# ph_v6.net
KiCad netlist of a schematic drawn in EAGLE
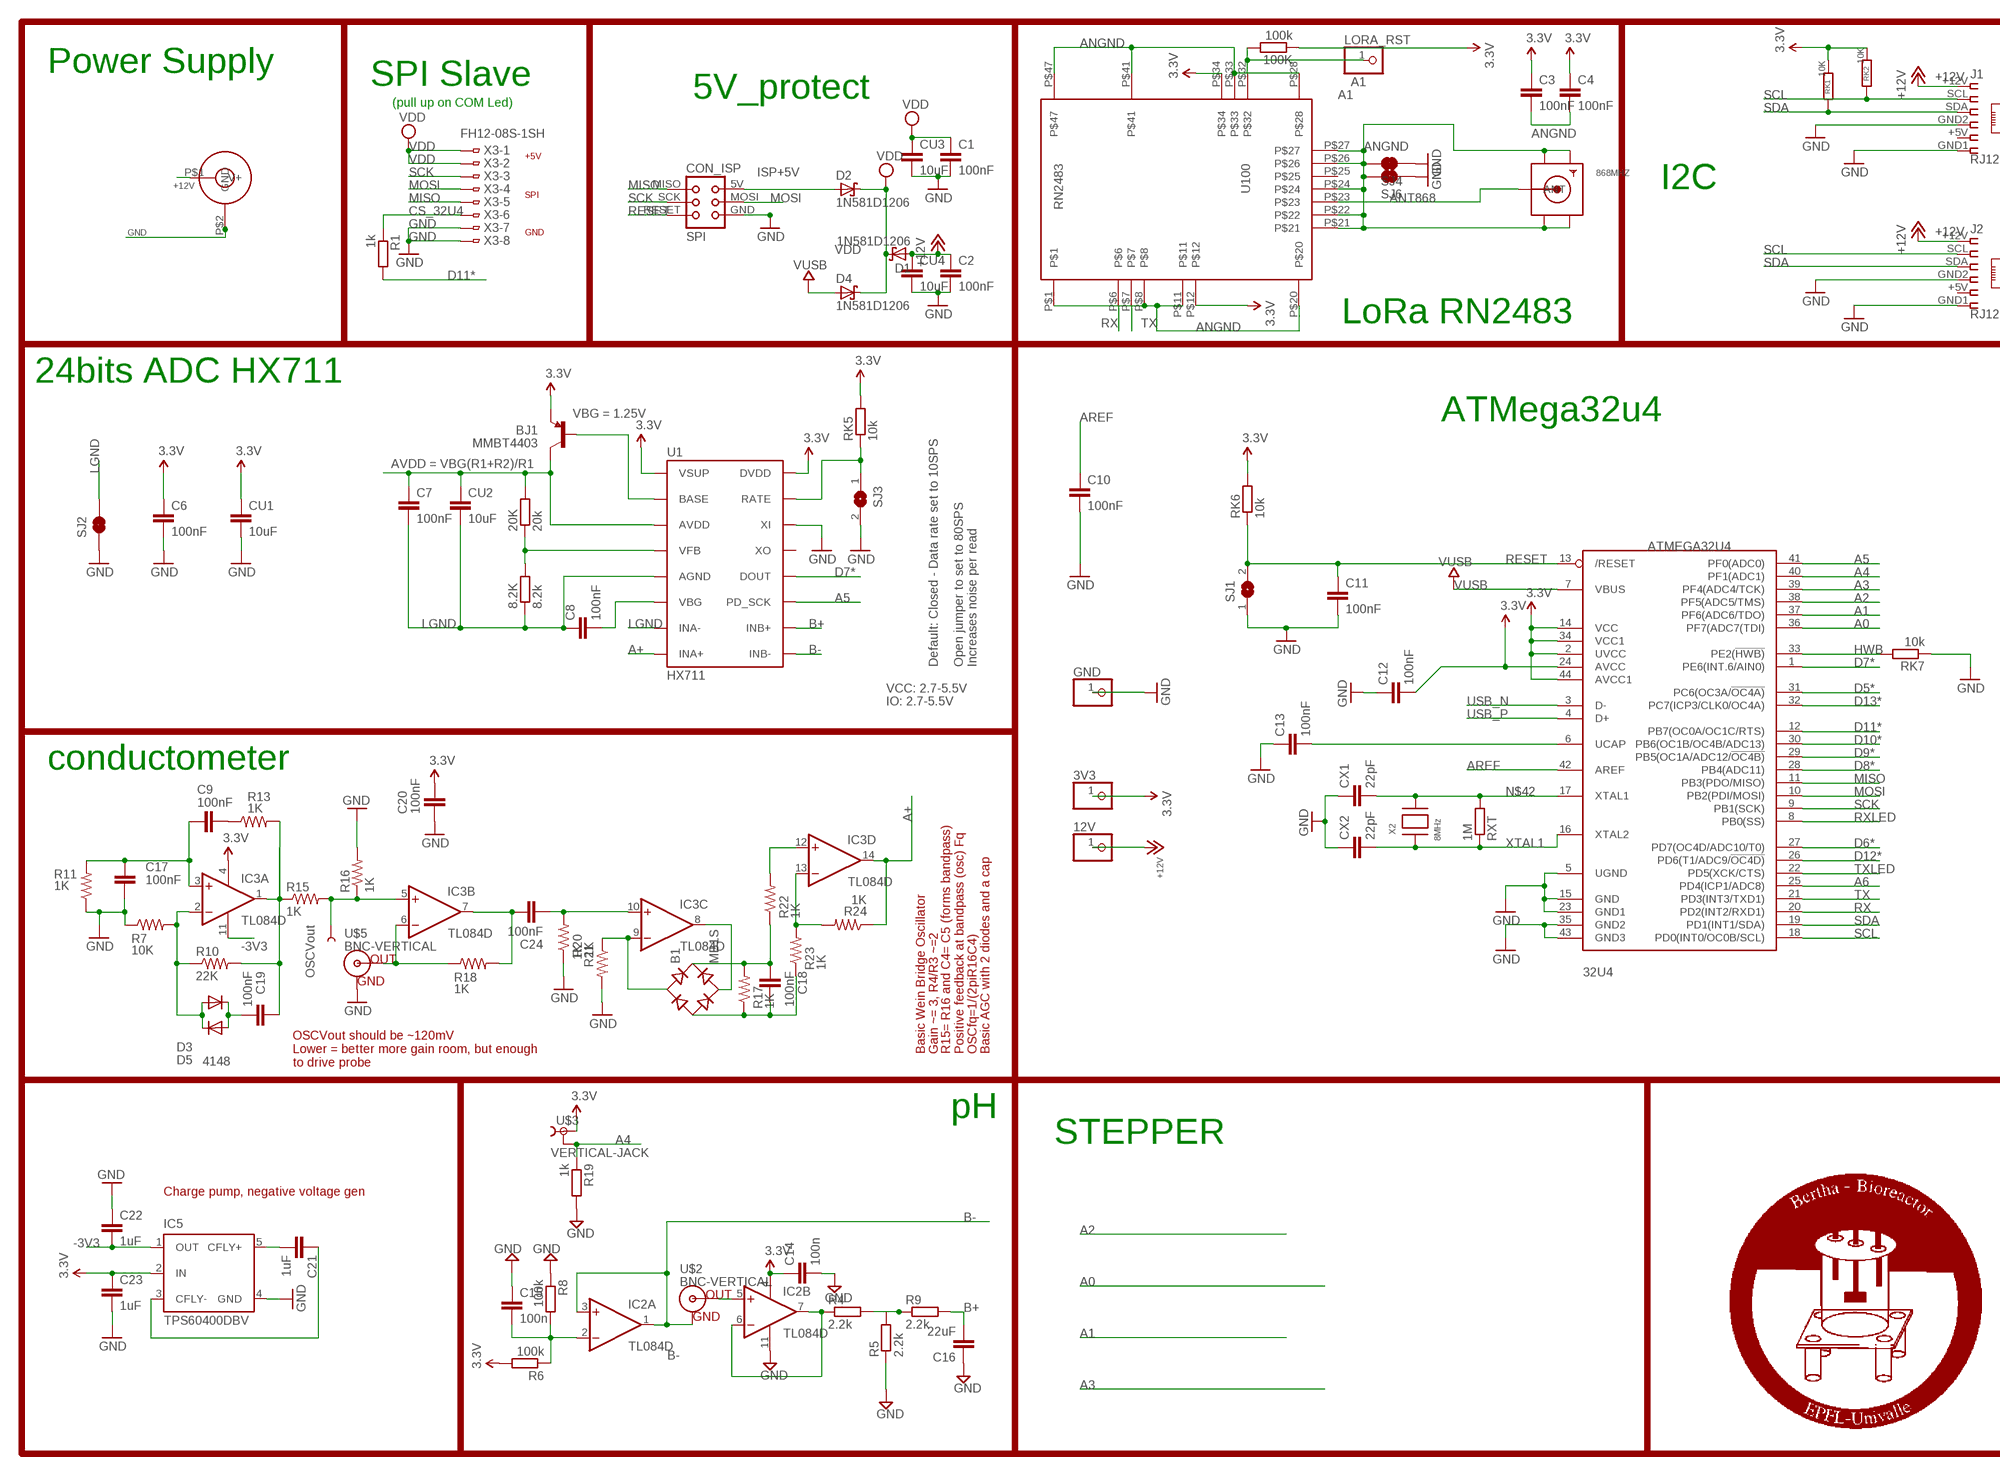
[diagram p0: schematic, sheet 1, part 1 of 2]
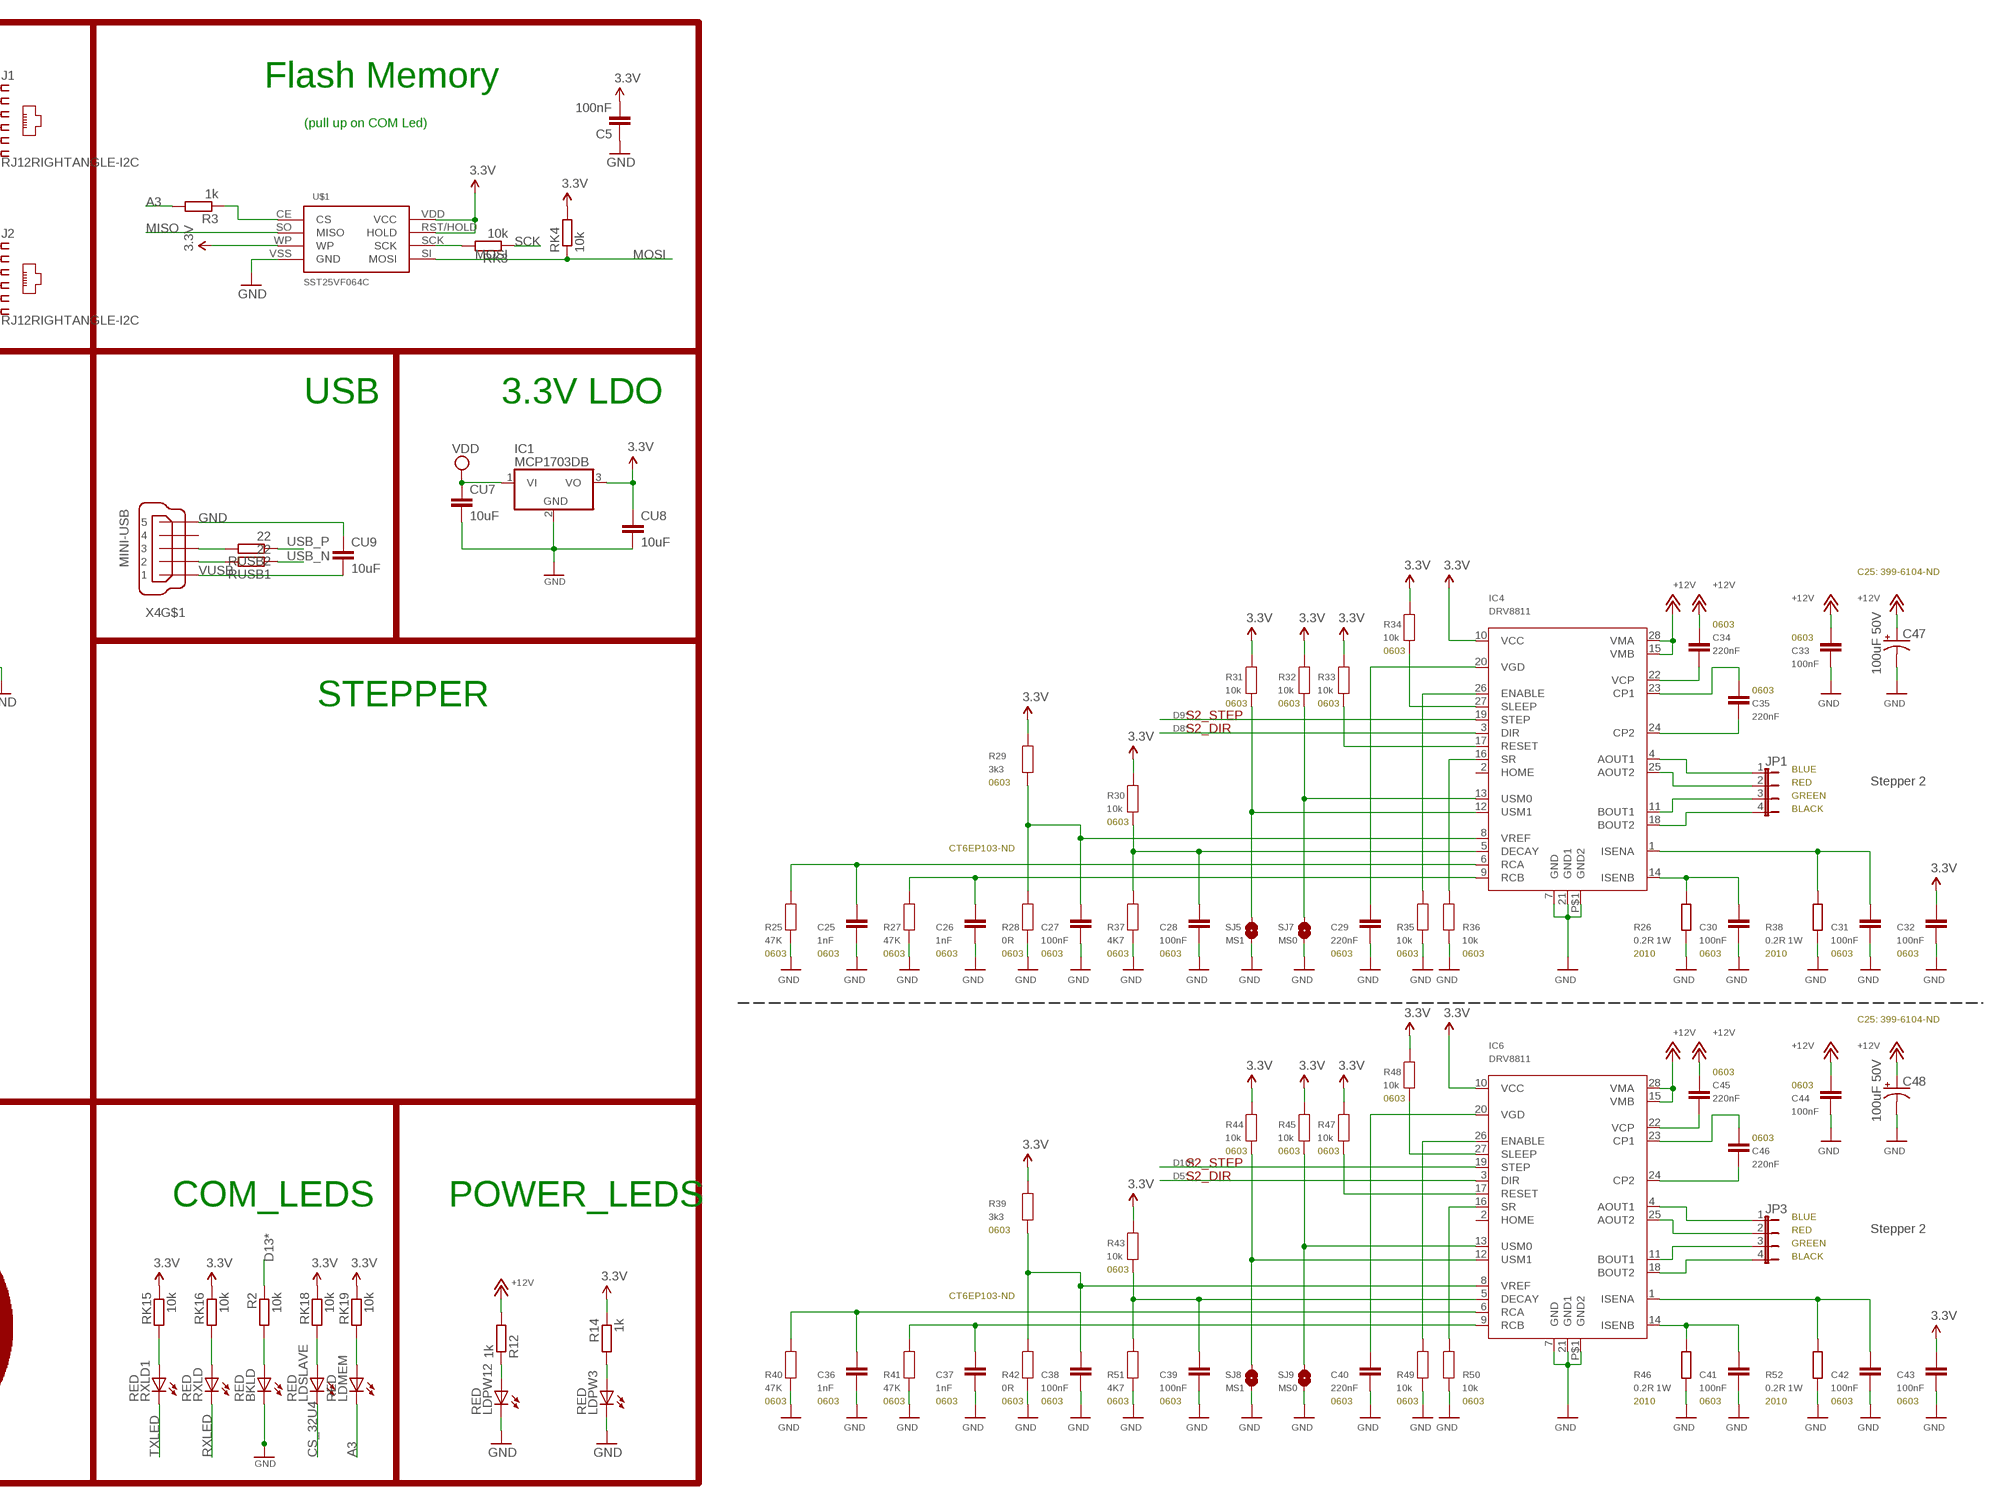
[diagram p1: schematic, sheet 1, part 2 of 2]

(export (version "E")
  (design (tool "Eeschema 10.0.6"))
  (components
    (comp (ref "3V3")
      (value "PINHD-1X1")
      (footprint "eagle-import:1X01")
      (libsource (lib "eagle-import") (part "PINHD-1X1"))
    )
    (comp (ref "8.2K")
      (value "8.2k")
      (footprint "eagle-import:R0805")
      (libsource (lib "eagle-import") (part "resistor_R-EU_R0805"))
    )
    (comp (ref "12V")
      (value "PINHD-1X1")
      (footprint "eagle-import:1X01")
      (libsource (lib "eagle-import") (part "PINHD-1X1"))
    )
    (comp (ref "20K")
      (value "20k")
      (footprint "eagle-import:R0805")
      (libsource (lib "eagle-import") (part "resistor_R-EU_R0805"))
    )
    (comp (ref "32U4")
      (value "ATMEGA32U4")
      (footprint "eagle-import:TQFP44")
      (libsource (lib "eagle-import") (part "ATMEGA32U4-AU"))
    )
    (comp (ref "100K")
      (value "100k")
      (footprint "eagle-import:R0805")
      (libsource (lib "eagle-import") (part "R-EU_R0805"))
    )
    (comp (ref "868MHZ")
      (value "SMACONNECTOR_EDGE")
      (footprint "eagle-import:SMA_EDGELAUNCH")
      (libsource (lib "eagle-import") (part "SMACONNECTOR_EDGE"))
    )
    (comp (ref "B1")
      (value "MB1S")
      (footprint "eagle-import:SOIC-4")
      (libsource (lib "eagle-import") (part "MBS1"))
    )
    (comp (ref "BJ1")
      (value "MMBT4403")
      (footprint "eagle-import:SOT23-3")
      (libsource (lib "eagle-import") (part "TRANSISTOR_PNPMMBT4403"))
    )
    (comp (ref "BKLD")
      (value "RED")
      (footprint "eagle-import:CHIP-LED0805")
      (libsource (lib "eagle-import") (part "LEDCHIP-LED0805"))
    )
    (comp (ref "C1")
      (value "100nF")
      (footprint "eagle-import:C0805")
      (libsource (lib "eagle-import") (part "C-EUC0805"))
    )
    (comp (ref "C2")
      (value "100nF")
      (footprint "eagle-import:C0805")
      (libsource (lib "eagle-import") (part "C-EUC0805"))
    )
    (comp (ref "C3")
      (value "100nF")
      (footprint "eagle-import:C0805")
      (libsource (lib "eagle-import") (part "C-EUC0805"))
    )
    (comp (ref "C4")
      (value "100nF")
      (footprint "eagle-import:C0805")
      (libsource (lib "eagle-import") (part "C-EUC0805"))
    )
    (comp (ref "C5")
      (value "100nF")
      (footprint "eagle-import:C0805")
      (libsource (lib "eagle-import") (part "C-EUC0805"))
    )
    (comp (ref "C6")
      (value "100nF")
      (footprint "eagle-import:C0805")
      (libsource (lib "eagle-import") (part "C-EUC0805"))
    )
    (comp (ref "C7")
      (value "100nF")
      (footprint "eagle-import:C0805")
      (libsource (lib "eagle-import") (part "C-EUC0805"))
    )
    (comp (ref "C8")
      (value "100nF")
      (footprint "eagle-import:C0805")
      (libsource (lib "eagle-import") (part "C-EUC0805"))
    )
    (comp (ref "C9")
      (value "100nF")
      (footprint "eagle-import:0805")
      (libsource (lib "eagle-import") (part "CAP0805"))
    )
    (comp (ref "C10")
      (value "100nF")
      (footprint "eagle-import:C0805")
      (libsource (lib "eagle-import") (part "C-EUC0805"))
    )
    (comp (ref "C11")
      (value "100nF")
      (footprint "eagle-import:C0805")
      (libsource (lib "eagle-import") (part "C-EUC0805"))
    )
    (comp (ref "C12")
      (value "100nF")
      (footprint "eagle-import:C0805")
      (libsource (lib "eagle-import") (part "C-EUC0805"))
    )
    (comp (ref "C13")
      (value "100nF")
      (footprint "eagle-import:C0805")
      (libsource (lib "eagle-import") (part "C-EUC0805"))
    )
    (comp (ref "C14")
      (value "100n")
      (footprint "eagle-import:C0805")
      (libsource (lib "eagle-import") (part "C-EUC0805"))
    )
    (comp (ref "C15")
      (value "100n")
      (footprint "eagle-import:C0805")
      (libsource (lib "eagle-import") (part "C-EUC0805"))
    )
    (comp (ref "C16")
      (value "22uF")
      (footprint "eagle-import:C0805")
      (libsource (lib "eagle-import") (part "C-EUC0805"))
    )
    (comp (ref "C17")
      (value "100nF")
      (footprint "eagle-import:0805")
      (libsource (lib "eagle-import") (part "CAP0805"))
    )
    (comp (ref "C18")
      (value "100nF")
      (footprint "eagle-import:0805")
      (libsource (lib "eagle-import") (part "CAP0805"))
    )
    (comp (ref "C19")
      (value "100nF")
      (footprint "eagle-import:0805")
      (libsource (lib "eagle-import") (part "CAP0805"))
    )
    (comp (ref "C20")
      (value "100nF")
      (footprint "eagle-import:0805")
      (libsource (lib "eagle-import") (part "CAP0805"))
    )
    (comp (ref "C21")
      (value "1uF")
      (footprint "eagle-import:0805")
      (libsource (lib "eagle-import") (part "CAP0805"))
    )
    (comp (ref "C22")
      (value "1uF")
      (footprint "eagle-import:0805")
      (libsource (lib "eagle-import") (part "CAP0805"))
    )
    (comp (ref "C23")
      (value "1uF")
      (footprint "eagle-import:0805")
      (libsource (lib "eagle-import") (part "CAP0805"))
    )
    (comp (ref "C24")
      (value "100nF")
      (footprint "eagle-import:0805")
      (libsource (lib "eagle-import") (part "CAP0805"))
    )
    (comp (ref "C25")
      (value "1nF")
      (footprint "eagle-import:0805")
      (libsource (lib "eagle-import") (part "freetronics-master-v1_CAP0805"))
    )
    (comp (ref "C26")
      (value "1nF")
      (footprint "eagle-import:0805")
      (libsource (lib "eagle-import") (part "freetronics-master-v1_CAP0805"))
    )
    (comp (ref "C27")
      (value "100nF")
      (footprint "eagle-import:0805")
      (libsource (lib "eagle-import") (part "freetronics-master-v1_CAP0805"))
    )
    (comp (ref "C28")
      (value "100nF")
      (footprint "eagle-import:0805")
      (libsource (lib "eagle-import") (part "freetronics-master-v1_CAP0805"))
    )
    (comp (ref "C29")
      (value "220nF")
      (footprint "eagle-import:0805")
      (libsource (lib "eagle-import") (part "freetronics-master-v1_CAP0805"))
    )
    (comp (ref "C30")
      (value "100nF")
      (footprint "eagle-import:0603")
      (libsource (lib "eagle-import") (part "CAP0603"))
    )
    (comp (ref "C31")
      (value "100nF")
      (footprint "eagle-import:0805")
      (libsource (lib "eagle-import") (part "freetronics-master-v1_CAP0805"))
    )
    (comp (ref "C32")
      (value "100nF")
      (footprint "eagle-import:0805")
      (libsource (lib "eagle-import") (part "freetronics-master-v1_CAP0805"))
    )
    (comp (ref "C33")
      (value "100nF")
      (footprint "eagle-import:0805")
      (libsource (lib "eagle-import") (part "freetronics-master-v1_CAP0805"))
    )
    (comp (ref "C34")
      (value "220nF")
      (footprint "eagle-import:0805")
      (libsource (lib "eagle-import") (part "freetronics-master-v1_CAP0805"))
    )
    (comp (ref "C35")
      (value "220nF")
      (footprint "eagle-import:0805")
      (libsource (lib "eagle-import") (part "freetronics-master-v1_CAP0805"))
    )
    (comp (ref "C36")
      (value "1nF")
      (footprint "eagle-import:0805")
      (libsource (lib "eagle-import") (part "freetronics-master-v1_CAP0805"))
    )
    (comp (ref "C37")
      (value "1nF")
      (footprint "eagle-import:0805")
      (libsource (lib "eagle-import") (part "freetronics-master-v1_CAP0805"))
    )
    (comp (ref "C38")
      (value "100nF")
      (footprint "eagle-import:0805")
      (libsource (lib "eagle-import") (part "freetronics-master-v1_CAP0805"))
    )
    (comp (ref "C39")
      (value "100nF")
      (footprint "eagle-import:0805")
      (libsource (lib "eagle-import") (part "freetronics-master-v1_CAP0805"))
    )
    (comp (ref "C40")
      (value "220nF")
      (footprint "eagle-import:0805")
      (libsource (lib "eagle-import") (part "freetronics-master-v1_CAP0805"))
    )
    (comp (ref "C41")
      (value "100nF")
      (footprint "eagle-import:0603")
      (libsource (lib "eagle-import") (part "CAP0603"))
    )
    (comp (ref "C42")
      (value "100nF")
      (footprint "eagle-import:0805")
      (libsource (lib "eagle-import") (part "freetronics-master-v1_CAP0805"))
    )
    (comp (ref "C43")
      (value "100nF")
      (footprint "eagle-import:0805")
      (libsource (lib "eagle-import") (part "freetronics-master-v1_CAP0805"))
    )
    (comp (ref "C44")
      (value "100nF")
      (footprint "eagle-import:0805")
      (libsource (lib "eagle-import") (part "freetronics-master-v1_CAP0805"))
    )
    (comp (ref "C45")
      (value "220nF")
      (footprint "eagle-import:0805")
      (libsource (lib "eagle-import") (part "freetronics-master-v1_CAP0805"))
    )
    (comp (ref "C46")
      (value "220nF")
      (footprint "eagle-import:0805")
      (libsource (lib "eagle-import") (part "freetronics-master-v1_CAP0805"))
    )
    (comp (ref "C47")
      (value "100uF 50V")
      (footprint "eagle-import:PANASONIC_E")
      (libsource (lib "eagle-import") (part "CAP_POLE"))
    )
    (comp (ref "C48")
      (value "100uF 50V")
      (footprint "eagle-import:PANASONIC_E")
      (libsource (lib "eagle-import") (part "CAP_POLE"))
    )
    (comp (ref "CON1")
      (value "JACK_DC_BARREL")
      (footprint "eagle-import:DC_BARREL")
      (libsource (lib "eagle-import") (part "JACK_DC_BARREL"))
    )
    (comp (ref "CON_ISP")
      (value "SPI")
      (footprint "eagle-import:TC2030-MCP-NL")
      (libsource (lib "eagle-import") (part "TINYISPT"))
    )
    (comp (ref "CU1")
      (value "10uF")
      (footprint "eagle-import:C0805")
      (libsource (lib "eagle-import") (part "C-EUC0805"))
    )
    (comp (ref "CU2")
      (value "10uF")
      (footprint "eagle-import:C0805")
      (libsource (lib "eagle-import") (part "C-EUC0805"))
    )
    (comp (ref "CU3")
      (value "10uF")
      (footprint "eagle-import:C0805")
      (libsource (lib "eagle-import") (part "C-EUC0805"))
    )
    (comp (ref "CU4")
      (value "10uF")
      (footprint "eagle-import:C0805")
      (libsource (lib "eagle-import") (part "C-EUC0805"))
    )
    (comp (ref "CU7")
      (value "10uF")
      (footprint "eagle-import:C0805")
      (libsource (lib "eagle-import") (part "C-EUC0805"))
    )
    (comp (ref "CU8")
      (value "10uF")
      (footprint "eagle-import:C0805")
      (libsource (lib "eagle-import") (part "C-EUC0805"))
    )
    (comp (ref "CU9")
      (value "10uF")
      (footprint "eagle-import:C0805")
      (libsource (lib "eagle-import") (part "C-EUC0805"))
    )
    (comp (ref "CX1")
      (value "22pF")
      (footprint "eagle-import:C0805")
      (libsource (lib "eagle-import") (part "C-EUC0805"))
    )
    (comp (ref "CX2")
      (value "22pF")
      (footprint "eagle-import:C0805")
      (libsource (lib "eagle-import") (part "C-EUC0805"))
    )
    (comp (ref "D1")
      (value "1N581D1206")
      (footprint "eagle-import:LED-1206")
      (libsource (lib "eagle-import") (part "1N581D1206"))
    )
    (comp (ref "D2")
      (value "1N581D1206")
      (footprint "eagle-import:LED-1206")
      (libsource (lib "eagle-import") (part "1N581D1206"))
    )
    (comp (ref "D3")
      (value "4148")
      (footprint "eagle-import:SOD123")
      (libsource (lib "eagle-import") (part "MBR0520LT"))
    )
    (comp (ref "D4")
      (value "1N581D1206")
      (footprint "eagle-import:LED-1206")
      (libsource (lib "eagle-import") (part "1N581D1206"))
    )
    (comp (ref "D5")
      (value "4148")
      (footprint "eagle-import:SOD123")
      (libsource (lib "eagle-import") (part "MBR0520LT"))
    )
    (comp (ref "GND")
      (value "PINHD-1X1")
      (footprint "eagle-import:1X01")
      (libsource (lib "eagle-import") (part "PINHD-1X1"))
    )
    (comp (ref "IC1")
      (value "MCP1703DB")
      (footprint "eagle-import:SOT223")
      (libsource (lib "eagle-import") (part "MCP1703DB"))
    )
    (comp (ref "IC2")
      (value "TL084D")
      (footprint "eagle-import:SO14")
      (libsource (lib "eagle-import") (part "TL084D"))
    )
    (comp (ref "IC3")
      (value "TL084D")
      (footprint "eagle-import:SO14")
      (libsource (lib "eagle-import") (part "TL084D"))
    )
    (comp (ref "IC4")
      (value "DRV8811")
      (footprint "eagle-import:HTSSOP28")
      (libsource (lib "eagle-import") (part "DRV8811"))
    )
    (comp (ref "IC5")
      (value "TPS60400DBV")
      (footprint "eagle-import:SOT23-DBV")
      (libsource (lib "eagle-import") (part "TPS60400DBV"))
    )
    (comp (ref "IC6")
      (value "DRV8811")
      (footprint "eagle-import:HTSSOP28")
      (libsource (lib "eagle-import") (part "DRV8811"))
    )
    (comp (ref "J1")
      (value "RJ12RIGHTANGLE-I2C")
      (footprint "eagle-import:RJ12-RIGHTANGLE-I2C")
      (libsource (lib "eagle-import") (part "RJ12RIGHTANGLE-I2C"))
    )
    (comp (ref "J2")
      (value "RJ12RIGHTANGLE-I2C")
      (footprint "eagle-import:RJ12-RIGHTANGLE-I2C")
      (libsource (lib "eagle-import") (part "RJ12RIGHTANGLE-I2C"))
    )
    (comp (ref "JP1")
      (value "JP4E")
      (footprint "eagle-import:JP4")
      (libsource (lib "eagle-import") (part "JP4E"))
    )
    (comp (ref "JP3")
      (value "JP4E")
      (footprint "eagle-import:JP4")
      (libsource (lib "eagle-import") (part "JP4E"))
    )
    (comp (ref "LDMEM")
      (value "RED")
      (footprint "eagle-import:CHIP-LED0805")
      (libsource (lib "eagle-import") (part "LEDCHIP-LED0805"))
    )
    (comp (ref "LDPW3")
      (value "RED")
      (footprint "eagle-import:CHIP-LED0805")
      (libsource (lib "eagle-import") (part "LEDCHIP-LED0805"))
    )
    (comp (ref "LDPW12")
      (value "RED")
      (footprint "eagle-import:CHIP-LED0805")
      (libsource (lib "eagle-import") (part "LEDCHIP-LED0805"))
    )
    (comp (ref "LDSLAVE")
      (value "RED")
      (footprint "eagle-import:CHIP-LED0805")
      (libsource (lib "eagle-import") (part "LEDCHIP-LED0805"))
    )
    (comp (ref "LORA_RST")
      (value "PINHD-1X1")
      (footprint "eagle-import:1X01")
      (libsource (lib "eagle-import") (part "PINHD-1X1"))
    )
    (comp (ref "R1")
      (value "1k")
      (footprint "eagle-import:R0805")
      (libsource (lib "eagle-import") (part "R-EU_R0805"))
    )
    (comp (ref "R2")
      (value "10k")
      (footprint "eagle-import:R0805")
      (libsource (lib "eagle-import") (part "R-EU_R0805"))
    )
    (comp (ref "R3")
      (value "1k")
      (footprint "eagle-import:R0805")
      (libsource (lib "eagle-import") (part "R-EU_R0805"))
    )
    (comp (ref "R4")
      (value "2.2k")
      (footprint "eagle-import:R0805")
      (libsource (lib "eagle-import") (part "resistor_R-EU_R0805"))
    )
    (comp (ref "R5")
      (value "2.2k")
      (footprint "eagle-import:R0805")
      (libsource (lib "eagle-import") (part "resistor_R-EU_R0805"))
    )
    (comp (ref "R6")
      (value "100k")
      (footprint "eagle-import:R0805")
      (libsource (lib "eagle-import") (part "resistor_R-EU_R0805"))
    )
    (comp (ref "R7")
      (value "10K")
      (footprint "eagle-import:0805")
      (libsource (lib "eagle-import") (part "RESISTOR0805-RES"))
    )
    (comp (ref "R8")
      (value "100k")
      (footprint "eagle-import:R0805")
      (libsource (lib "eagle-import") (part "resistor_R-EU_R0805"))
    )
    (comp (ref "R9")
      (value "2.2k")
      (footprint "eagle-import:R0805")
      (libsource (lib "eagle-import") (part "resistor_R-EU_R0805"))
    )
    (comp (ref "R10")
      (value "22K")
      (footprint "eagle-import:0805")
      (libsource (lib "eagle-import") (part "RESISTOR0805-RES"))
    )
    (comp (ref "R11")
      (value "1K")
      (footprint "eagle-import:0805")
      (libsource (lib "eagle-import") (part "RESISTOR0805-RES"))
    )
    (comp (ref "R12")
      (value "1k")
      (footprint "eagle-import:R0805")
      (libsource (lib "eagle-import") (part "R-EU_R0805"))
    )
    (comp (ref "R13")
      (value "1K")
      (footprint "eagle-import:0805")
      (libsource (lib "eagle-import") (part "RESISTOR0805-RES"))
    )
    (comp (ref "R14")
      (value "1k")
      (footprint "eagle-import:R0805")
      (libsource (lib "eagle-import") (part "resistor_R-EU_R0805"))
    )
    (comp (ref "R15")
      (value "1K")
      (footprint "eagle-import:0805")
      (libsource (lib "eagle-import") (part "RESISTOR0805-RES"))
    )
    (comp (ref "R16")
      (value "1K")
      (footprint "eagle-import:0805")
      (libsource (lib "eagle-import") (part "RESISTOR0805-RES"))
    )
    (comp (ref "R17")
      (value "1K")
      (footprint "eagle-import:0805")
      (libsource (lib "eagle-import") (part "RESISTOR0805-RES"))
    )
    (comp (ref "R18")
      (value "1K")
      (footprint "eagle-import:0805")
      (libsource (lib "eagle-import") (part "RESISTOR0805-RES"))
    )
    (comp (ref "R19")
      (value "1k")
      (footprint "eagle-import:R0805")
      (libsource (lib "eagle-import") (part "resistor_R-EU_R0805"))
    )
    (comp (ref "R20")
      (value "1K")
      (footprint "eagle-import:0805")
      (libsource (lib "eagle-import") (part "RESISTOR0805-RES"))
    )
    (comp (ref "R21")
      (value "1K")
      (footprint "eagle-import:0805")
      (libsource (lib "eagle-import") (part "RESISTOR0805-RES"))
    )
    (comp (ref "R22")
      (value "1K")
      (footprint "eagle-import:0805")
      (libsource (lib "eagle-import") (part "RESISTOR0805-RES"))
    )
    (comp (ref "R23")
      (value "1K")
      (footprint "eagle-import:0805")
      (libsource (lib "eagle-import") (part "RESISTOR0805-RES"))
    )
    (comp (ref "R24")
      (value "1K")
      (footprint "eagle-import:0805")
      (libsource (lib "eagle-import") (part "RESISTOR0805-RES"))
    )
    (comp (ref "R25")
      (value "47K")
      (footprint "eagle-import:0805")
      (libsource (lib "eagle-import") (part "RESISTOR0805"))
    )
    (comp (ref "R26")
      (value "0.2R 1W")
      (footprint "eagle-import:R2010")
      (libsource (lib "eagle-import") (part "R-EU_R2010"))
    )
    (comp (ref "R27")
      (value "47K")
      (footprint "eagle-import:0805")
      (libsource (lib "eagle-import") (part "RESISTOR0805"))
    )
    (comp (ref "R28")
      (value "0R")
      (footprint "eagle-import:0805")
      (libsource (lib "eagle-import") (part "RESISTOR0805"))
    )
    (comp (ref "R29")
      (value "3k3")
      (footprint "eagle-import:0805")
      (libsource (lib "eagle-import") (part "RESISTOR0805"))
    )
    (comp (ref "R30")
      (value "10k")
      (footprint "eagle-import:0805")
      (libsource (lib "eagle-import") (part "RESISTOR0805"))
    )
    (comp (ref "R31")
      (value "10k")
      (footprint "eagle-import:0805")
      (libsource (lib "eagle-import") (part "RESISTOR0805"))
    )
    (comp (ref "R32")
      (value "10k")
      (footprint "eagle-import:0805")
      (libsource (lib "eagle-import") (part "RESISTOR0805"))
    )
    (comp (ref "R33")
      (value "10k")
      (footprint "eagle-import:0805")
      (libsource (lib "eagle-import") (part "RESISTOR0805"))
    )
    (comp (ref "R34")
      (value "10k")
      (footprint "eagle-import:0805")
      (libsource (lib "eagle-import") (part "RESISTOR0805"))
    )
    (comp (ref "R35")
      (value "10k")
      (footprint "eagle-import:0805")
      (libsource (lib "eagle-import") (part "RESISTOR0805"))
    )
    (comp (ref "R36")
      (value "10k")
      (footprint "eagle-import:0805")
      (libsource (lib "eagle-import") (part "RESISTOR0805"))
    )
    (comp (ref "R37")
      (value "4K7")
      (footprint "eagle-import:0805")
      (libsource (lib "eagle-import") (part "RESISTOR0805"))
    )
    (comp (ref "R38")
      (value "0.2R 1W")
      (footprint "eagle-import:R2010")
      (libsource (lib "eagle-import") (part "R-EU_R2010"))
    )
    (comp (ref "R39")
      (value "3k3")
      (footprint "eagle-import:0805")
      (libsource (lib "eagle-import") (part "RESISTOR0805"))
    )
    (comp (ref "R40")
      (value "47K")
      (footprint "eagle-import:0805")
      (libsource (lib "eagle-import") (part "RESISTOR0805"))
    )
    (comp (ref "R41")
      (value "47K")
      (footprint "eagle-import:0805")
      (libsource (lib "eagle-import") (part "RESISTOR0805"))
    )
    (comp (ref "R42")
      (value "0R")
      (footprint "eagle-import:0805")
      (libsource (lib "eagle-import") (part "RESISTOR0805"))
    )
    (comp (ref "R43")
      (value "10k")
      (footprint "eagle-import:0805")
      (libsource (lib "eagle-import") (part "RESISTOR0805"))
    )
    (comp (ref "R44")
      (value "10k")
      (footprint "eagle-import:0805")
      (libsource (lib "eagle-import") (part "RESISTOR0805"))
    )
    (comp (ref "R45")
      (value "10k")
      (footprint "eagle-import:0805")
      (libsource (lib "eagle-import") (part "RESISTOR0805"))
    )
    (comp (ref "R46")
      (value "0.2R 1W")
      (footprint "eagle-import:R2010")
      (libsource (lib "eagle-import") (part "R-EU_R2010"))
    )
    (comp (ref "R47")
      (value "10k")
      (footprint "eagle-import:0805")
      (libsource (lib "eagle-import") (part "RESISTOR0805"))
    )
    (comp (ref "R48")
      (value "10k")
      (footprint "eagle-import:0805")
      (libsource (lib "eagle-import") (part "RESISTOR0805"))
    )
    (comp (ref "R49")
      (value "10k")
      (footprint "eagle-import:0805")
      (libsource (lib "eagle-import") (part "RESISTOR0805"))
    )
    (comp (ref "R50")
      (value "10k")
      (footprint "eagle-import:0805")
      (libsource (lib "eagle-import") (part "RESISTOR0805"))
    )
    (comp (ref "R51")
      (value "4K7")
      (footprint "eagle-import:0805")
      (libsource (lib "eagle-import") (part "RESISTOR0805"))
    )
    (comp (ref "R52")
      (value "0.2R 1W")
      (footprint "eagle-import:R2010")
      (libsource (lib "eagle-import") (part "R-EU_R2010"))
    )
    (comp (ref "RK1")
      (value "10K")
      (footprint "eagle-import:M0805")
      (libsource (lib "eagle-import") (part "resistor_R-EU_M0805"))
    )
    (comp (ref "RK2")
      (value "10K")
      (footprint "eagle-import:M0805")
      (libsource (lib "eagle-import") (part "resistor_R-EU_M0805"))
    )
    (comp (ref "RK3")
      (value "10k")
      (footprint "eagle-import:R0805")
      (libsource (lib "eagle-import") (part "R-EU_R0805"))
    )
    (comp (ref "RK4")
      (value "10k")
      (footprint "eagle-import:R0805")
      (libsource (lib "eagle-import") (part "R-EU_R0805"))
    )
    (comp (ref "RK5")
      (value "10k")
      (footprint "eagle-import:R0805")
      (libsource (lib "eagle-import") (part "resistor_R-EU_R0805"))
    )
    (comp (ref "RK6")
      (value "10k")
      (footprint "eagle-import:M0805")
      (libsource (lib "eagle-import") (part "resistor_R-EU_M0805"))
    )
    (comp (ref "RK7")
      (value "10k")
      (footprint "eagle-import:M0805")
      (libsource (lib "eagle-import") (part "resistor_R-EU_M0805"))
    )
    (comp (ref "RK15")
      (value "10k")
      (footprint "eagle-import:R0805")
      (libsource (lib "eagle-import") (part "R-EU_R0805"))
    )
    (comp (ref "RK16")
      (value "10k")
      (footprint "eagle-import:R0805")
      (libsource (lib "eagle-import") (part "R-EU_R0805"))
    )
    (comp (ref "RK18")
      (value "10k")
      (footprint "eagle-import:R0805")
      (libsource (lib "eagle-import") (part "R-EU_R0805"))
    )
    (comp (ref "RK19")
      (value "10k")
      (footprint "eagle-import:R0805")
      (libsource (lib "eagle-import") (part "R-EU_R0805"))
    )
    (comp (ref "RUSB1")
      (value "22")
      (footprint "eagle-import:M1206")
      (libsource (lib "eagle-import") (part "resistor_R-EU_M1206"))
    )
    (comp (ref "RUSB2")
      (value "22")
      (footprint "eagle-import:M1206")
      (libsource (lib "eagle-import") (part "resistor_R-EU_M1206"))
    )
    (comp (ref "RXLD")
      (value "RED")
      (footprint "eagle-import:CHIP-LED0805")
      (libsource (lib "eagle-import") (part "LEDCHIP-LED0805"))
    )
    (comp (ref "RXLD1")
      (value "RED")
      (footprint "eagle-import:CHIP-LED0805")
      (libsource (lib "eagle-import") (part "LEDCHIP-LED0805"))
    )
    (comp (ref "RXT")
      (value "1M")
      (footprint "eagle-import:R0805")
      (libsource (lib "eagle-import") (part "R-EU_R0805"))
    )
    (comp (ref "SJ1")
      (value "SJ")
      (footprint "eagle-import:SJ")
      (libsource (lib "eagle-import") (part "jumper_SJ"))
    )
    (comp (ref "SJ2")
      (value "JUMPER-PAD-2-NC_BY_TRACE")
      (footprint "eagle-import:PAD-JUMPER-2-NC_BY_TRACE_YES_SILK")
      (libsource (lib "eagle-import") (part "JUMPER-PAD-2-NC_BY_TRACE"))
    )
    (comp (ref "SJ3")
      (value "SJ")
      (footprint "eagle-import:SJ")
      (libsource (lib "eagle-import") (part "jumper_SJ"))
    )
    (comp (ref "SJ4")
      (value "JUMPER-PAD-2-NC_BY_TRACE")
      (footprint "eagle-import:PAD-JUMPER-2-NC_BY_TRACE_YES_SILK")
      (libsource (lib "eagle-import") (part "JUMPER-PAD-2-NC_BY_TRACE"))
    )
    (comp (ref "SJ5")
      (value "MS1")
      (footprint "eagle-import:SJ")
      (libsource (lib "eagle-import") (part "SJ"))
    )
    (comp (ref "SJ6")
      (value "JUMPER-PAD-2-NC_BY_TRACE")
      (footprint "eagle-import:PAD-JUMPER-2-NC_BY_TRACE_YES_SILK")
      (libsource (lib "eagle-import") (part "JUMPER-PAD-2-NC_BY_TRACE"))
    )
    (comp (ref "SJ7")
      (value "MS0")
      (footprint "eagle-import:SJ")
      (libsource (lib "eagle-import") (part "SJ"))
    )
    (comp (ref "SJ8")
      (value "MS1")
      (footprint "eagle-import:SJ")
      (libsource (lib "eagle-import") (part "SJ"))
    )
    (comp (ref "SJ9")
      (value "MS0")
      (footprint "eagle-import:SJ")
      (libsource (lib "eagle-import") (part "SJ"))
    )
    (comp (ref "TP5")
      (value "OSCVout")
      (footprint "eagle-import:PAD.03X.03")
      (libsource (lib "eagle-import") (part "TEST-POINT3"))
    )
    (comp (ref "U$1")
      (value "SST25VF064C")
      (footprint "eagle-import:SOIC_8-LEAD")
      (libsource (lib "eagle-import") (part "SST25VF064C"))
    )
    (comp (ref "U$2")
      (value "BNC-VERTICAL")
      (footprint "eagle-import:BNC-VERTICAL")
      (libsource (lib "eagle-import") (part "BNC-VERTICAL"))
    )
    (comp (ref "U$3")
      (value "VERTICAL-JACK")
      (footprint "eagle-import:VERTICAL-JACK")
      (libsource (lib "eagle-import") (part "VERTICAL-JACK"))
    )
    (comp (ref "U$5")
      (value "BNC-VERTICAL")
      (footprint "eagle-import:BNC-VERTICAL")
      (libsource (lib "eagle-import") (part "BNC-VERTICAL"))
    )
    (comp (ref "U1")
      (value "HX711")
      (footprint "eagle-import:SO16")
      (libsource (lib "eagle-import") (part "HX711HX711"))
    )
    (comp (ref "U100")
      (value "RN2483")
      (footprint "eagle-import:RN2483")
      (libsource (lib "eagle-import") (part "RN2483"))
    )
    (comp (ref "X2")
      (value "8MHz")
      (footprint "eagle-import:NX6035")
      (libsource (lib "eagle-import") (part "XTALNX6035"))
    )
    (comp (ref "X3")
      (value "FH12-08S-1SH")
      (footprint "eagle-import:FH12-08S-1SH")
      (libsource (lib "eagle-import") (part "FH12-08S-1SH"))
    )
    (comp (ref "X4")
      (value "MINI-USB")
      (footprint "eagle-import:32005-201")
      (libsource (lib "eagle-import") (part "MINI-USB-SCHIELD-32005-201"))
    )
  )
  (nets
    (net (code "1") (name "+12V") (class "Default")
      (node (ref "12V") (pin "1") (pinfunction "1_1") (pintype "passive"))
      (node (ref "C2") (pin "1") (pinfunction "1_1") (pintype "passive"))
      (node (ref "C33") (pin "1") (pinfunction "1_1") (pintype "passive"))
      (node (ref "C34") (pin "1") (pinfunction "1_1") (pintype "passive"))
      (node (ref "C44") (pin "1") (pinfunction "1_1") (pintype "passive"))
      (node (ref "C45") (pin "1") (pinfunction "1_1") (pintype "passive"))
      (node (ref "C47") (pin "+") (pinfunction "+_+") (pintype "passive"))
      (node (ref "C48") (pin "+") (pinfunction "+_+") (pintype "passive"))
      (node (ref "CON1") (pin "P$1") (pinfunction "V+_P$1") (pintype "bidirectional"))
      (node (ref "CU4") (pin "1") (pinfunction "1_1") (pintype "passive"))
      (node (ref "D1") (pin "A") (pinfunction "A_A") (pintype "passive"))
      (node (ref "IC4") (pin "15") (pinfunction "VMB_15") (pintype "bidirectional"))
      (node (ref "IC4") (pin "28") (pinfunction "VMA_28") (pintype "bidirectional"))
      (node (ref "IC6") (pin "15") (pinfunction "VMB_15") (pintype "bidirectional"))
      (node (ref "IC6") (pin "28") (pinfunction "VMA_28") (pintype "bidirectional"))
      (node (ref "J1") (pin "+12V") (pinfunction "1_+12V") (pintype "bidirectional"))
      (node (ref "J2") (pin "+12V") (pinfunction "1_+12V") (pintype "bidirectional"))
      (node (ref "R12") (pin "2") (pinfunction "2_2") (pintype "passive"))
    )
    (net (code "2") (name "/-3V3") (class "Default")
      (node (ref "C22") (pin "2") (pinfunction "2_2") (pintype "passive"))
      (node (ref "IC3") (pin "11") (pinfunction "V-_11") (pintype "power_in"))
      (node (ref "IC5") (pin "1") (pinfunction "OUT_1") (pintype "input"))
    )
    (net (code "3") (name "/A+") (class "Default")
      (node (ref "IC3") (pin "14") (pinfunction "OUT_14") (pintype "output"))
      (node (ref "R24") (pin "1") (pinfunction "1_1") (pintype "passive"))
      (node (ref "U1") (pin "8") (pinfunction "INA+_8") (pintype "bidirectional"))
    )
    (net (code "4") (name "/A0") (class "Default")
      (node (ref "32U4") (pin "36") (pinfunction "PF7(ADC7(TDI)_36") (pintype "bidirectional"))
    )
    (net (code "5") (name "/A1") (class "Default")
      (node (ref "100K") (pin "2") (pinfunction "2_2") (pintype "passive"))
      (node (ref "32U4") (pin "37") (pinfunction "PF6(ADC6/TDO)_37") (pintype "bidirectional"))
      (node (ref "LORA_RST") (pin "1") (pinfunction "1_1") (pintype "passive"))
      (node (ref "U100") (pin "P$32") (pinfunction "P$32_P$32") (pintype "bidirectional"))
    )
    (net (code "6") (name "/A2") (class "Default")
      (node (ref "32U4") (pin "38") (pinfunction "PF5(ADC5/TMS)_38") (pintype "bidirectional"))
    )
    (net (code "7") (name "/A3") (class "Default")
      (node (ref "32U4") (pin "39") (pinfunction "PF4(ADC4/TCK)_39") (pintype "bidirectional"))
      (node (ref "LDMEM") (pin "C") (pinfunction "C_C") (pintype "passive"))
      (node (ref "R3") (pin "2") (pinfunction "2_2") (pintype "passive"))
    )
    (net (code "8") (name "/A4") (class "Default")
      (node (ref "32U4") (pin "40") (pinfunction "PF1(ADC1)_40") (pintype "bidirectional"))
      (node (ref "R19") (pin "1") (pinfunction "1_1") (pintype "passive"))
      (node (ref "U$3") (pin "P$2") (pinfunction "2_P$2") (pintype "passive"))
    )
    (net (code "9") (name "/A5") (class "Default")
      (node (ref "32U4") (pin "41") (pinfunction "PF0(ADC0)_41") (pintype "bidirectional"))
      (node (ref "U1") (pin "11") (pinfunction "PD_SCK_11") (pintype "bidirectional"))
    )
    (net (code "10") (name "/A6") (class "Default")
      (node (ref "32U4") (pin "25") (pinfunction "PD4(ICP1/ADC8)_25") (pintype "bidirectional"))
    )
    (net (code "11") (name "/ANGND") (class "Default")
      (node (ref "868MHZ") (pin "GND@1") (pinfunction "GND4_GND@1") (pintype "power_in"))
      (node (ref "868MHZ") (pin "GND@2") (pinfunction "GND3_GND@2") (pintype "power_in"))
      (node (ref "868MHZ") (pin "GND@3") (pinfunction "GND2_GND@3") (pintype "power_in"))
      (node (ref "868MHZ") (pin "GND@4") (pinfunction "GND1_GND@4") (pintype "power_in"))
      (node (ref "C3") (pin "2") (pinfunction "2_2") (pintype "passive"))
      (node (ref "C4") (pin "2") (pinfunction "2_2") (pintype "passive"))
      (node (ref "SJ4") (pin "2") (pinfunction "2_2") (pintype "passive"))
      (node (ref "SJ6") (pin "2") (pinfunction "2_2") (pintype "passive"))
      (node (ref "U100") (pin "P$1") (pinfunction "P$1_P$1") (pintype "bidirectional"))
      (node (ref "U100") (pin "P$11") (pinfunction "P$11_P$11") (pintype "bidirectional"))
      (node (ref "U100") (pin "P$20") (pinfunction "P$20_P$20") (pintype "bidirectional"))
      (node (ref "U100") (pin "P$21") (pinfunction "P$21_P$21") (pintype "bidirectional"))
      (node (ref "U100") (pin "P$22") (pinfunction "P$22_P$22") (pintype "bidirectional"))
      (node (ref "U100") (pin "P$24") (pinfunction "P$24_P$24") (pintype "bidirectional"))
      (node (ref "U100") (pin "P$26") (pinfunction "P$26_P$26") (pintype "bidirectional"))
      (node (ref "U100") (pin "P$27") (pinfunction "P$27_P$27") (pintype "bidirectional"))
      (node (ref "U100") (pin "P$28") (pinfunction "P$28_P$28") (pintype "bidirectional"))
      (node (ref "U100") (pin "P$33") (pinfunction "P$33_P$33") (pintype "bidirectional"))
      (node (ref "U100") (pin "P$41") (pinfunction "P$41_P$41") (pintype "bidirectional"))
      (node (ref "U100") (pin "P$47") (pinfunction "P$47_P$47") (pintype "bidirectional"))
      (node (ref "U100") (pin "P$8") (pinfunction "P$8_P$8") (pintype "bidirectional"))
    )
    (net (code "12") (name "/ANT868") (class "Default")
      (node (ref "868MHZ") (pin "P") (pinfunction "ANT_P") (pintype "bidirectional"))
      (node (ref "U100") (pin "P$23") (pinfunction "P$23_P$23") (pintype "bidirectional"))
    )
    (net (code "13") (name "/AREF") (class "Default")
      (node (ref "32U4") (pin "42") (pinfunction "AREF_42") (pintype "bidirectional"))
      (node (ref "C10") (pin "1") (pinfunction "1_1") (pintype "passive"))
    )
    (net (code "14") (name "/B+") (class "Default")
      (node (ref "C16") (pin "2") (pinfunction "2_2") (pintype "passive"))
      (node (ref "R9") (pin "2") (pinfunction "2_2") (pintype "passive"))
      (node (ref "U1") (pin "10") (pinfunction "INB+_10") (pintype "bidirectional"))
    )
    (net (code "15") (name "/B-") (class "Default")
      (node (ref "IC2") (pin "1") (pinfunction "OUT_1") (pintype "output"))
      (node (ref "IC2") (pin "3") (pinfunction "+IN_3") (pintype "input"))
      (node (ref "U$2") (pin "G") (pinfunction "GND_G") (pintype "bidirectional"))
      (node (ref "U1") (pin "9") (pinfunction "INB-_9") (pintype "bidirectional"))
    )
    (net (code "16") (name "/CS_32U4") (class "Default")
      (node (ref "LDSLAVE") (pin "C") (pinfunction "C_C") (pintype "passive"))
      (node (ref "R1") (pin "1") (pinfunction "1_1") (pintype "passive"))
      (node (ref "X3") (pin "6") (pinfunction "1_6") (pintype "passive"))
    )
    (net (code "17") (name "/D5*") (class "Default")
      (node (ref "32U4") (pin "31") (pinfunction "PC6(OC3A/~{OC4A})_31") (pintype "bidirectional"))
      (node (ref "IC6") (pin "3") (pinfunction "DIR_3") (pintype "bidirectional"))
    )
    (net (code "18") (name "/D6*") (class "Default")
      (node (ref "32U4") (pin "27") (pinfunction "PD7(OC4D/ADC10/T0)_27") (pintype "bidirectional"))
    )
    (net (code "19") (name "/D7*") (class "Default")
      (node (ref "32U4") (pin "1") (pinfunction "PE6(INT.6/AIN0)_1") (pintype "bidirectional"))
      (node (ref "U1") (pin "12") (pinfunction "DOUT_12") (pintype "bidirectional"))
    )
    (net (code "20") (name "/D8*") (class "Default")
      (node (ref "32U4") (pin "28") (pinfunction "PB4(ADC11)_28") (pintype "bidirectional"))
      (node (ref "IC4") (pin "3") (pinfunction "DIR_3") (pintype "bidirectional"))
    )
    (net (code "21") (name "/D9*") (class "Default")
      (node (ref "32U4") (pin "29") (pinfunction "PB5(OC1A/ADC12/~{OC4B})_29") (pintype "bidirectional"))
      (node (ref "IC4") (pin "19") (pinfunction "STEP_19") (pintype "bidirectional"))
    )
    (net (code "22") (name "/D10*") (class "Default")
      (node (ref "32U4") (pin "30") (pinfunction "PB6(OC1B/OC4B/ADC13)_30") (pintype "bidirectional"))
      (node (ref "IC6") (pin "19") (pinfunction "STEP_19") (pintype "bidirectional"))
    )
    (net (code "23") (name "/D11*") (class "Default")
      (node (ref "32U4") (pin "12") (pinfunction "PB7(OC0A/OC1C/RTS)_12") (pintype "bidirectional"))
      (node (ref "R1") (pin "2") (pinfunction "2_2") (pintype "passive"))
    )
    (net (code "24") (name "/D12*") (class "Default")
      (node (ref "32U4") (pin "26") (pinfunction "PD6(T1/ADC9/~{OC4D})_26") (pintype "bidirectional"))
    )
    (net (code "25") (name "/D13*") (class "Default")
      (node (ref "32U4") (pin "32") (pinfunction "PC7(ICP3/CLK0/OC4A)_32") (pintype "bidirectional"))
      (node (ref "R2") (pin "1") (pinfunction "1_1") (pintype "passive"))
    )
    (net (code "26") (name "/HWB") (class "Default")
      (node (ref "32U4") (pin "33") (pinfunction "PE2(~{HWB})_33") (pintype "bidirectional"))
      (node (ref "RK7") (pin "2") (pinfunction "2_2") (pintype "passive"))
    )
    (net (code "27") (name "/ISP+5V") (class "Default")
      (node (ref "CON_ISP") (pin "5V") (pinfunction "VCC_5V") (pintype "passive"))
      (node (ref "D2") (pin "A") (pinfunction "A_A") (pintype "passive"))
    )
    (net (code "28") (name "/LGND") (class "Default")
      (node (ref "8.2K") (pin "1") (pinfunction "1_1") (pintype "passive"))
      (node (ref "C7") (pin "2") (pinfunction "2_2") (pintype "passive"))
      (node (ref "C8") (pin "1") (pinfunction "1_1") (pintype "passive"))
      (node (ref "CU2") (pin "2") (pinfunction "2_2") (pintype "passive"))
      (node (ref "SJ2") (pin "2") (pinfunction "2_2") (pintype "passive"))
      (node (ref "U1") (pin "5") (pinfunction "AGND_5") (pintype "bidirectional"))
      (node (ref "U1") (pin "7") (pinfunction "INA-_7") (pintype "bidirectional"))
    )
    (net (code "29") (name "/MISO") (class "Default")
      (node (ref "32U4") (pin "11") (pinfunction "PB3(PDO/MISO)_11") (pintype "bidirectional"))
      (node (ref "CON_ISP") (pin "MISO") (pinfunction "MISO_MISO") (pintype "passive"))
      (node (ref "U$1") (pin "SO") (pinfunction "MISO_SO") (pintype "bidirectional"))
      (node (ref "X3") (pin "5") (pinfunction "1_5") (pintype "passive"))
    )
    (net (code "30") (name "/MOSI") (class "Default")
      (node (ref "32U4") (pin "10") (pinfunction "PB2(PDI/MOSI)_10") (pintype "bidirectional"))
      (node (ref "CON_ISP") (pin "MOSI") (pinfunction "MOSI_MOSI") (pintype "passive"))
      (node (ref "RK4") (pin "1") (pinfunction "1_1") (pintype "passive"))
      (node (ref "U$1") (pin "SI") (pinfunction "MOSI_SI") (pintype "bidirectional"))
      (node (ref "X3") (pin "4") (pinfunction "1_4") (pintype "passive"))
    )
    (net (code "31") (name "/N$42") (class "Default")
      (node (ref "32U4") (pin "17") (pinfunction "XTAL1_17") (pintype "bidirectional"))
      (node (ref "CX1") (pin "2") (pinfunction "2_2") (pintype "passive"))
      (node (ref "RXT") (pin "2") (pinfunction "2_2") (pintype "passive"))
      (node (ref "X2") (pin "P$2") (pinfunction "P$2_P$2") (pintype "bidirectional"))
    )
    (net (code "32") (name "/RESET") (class "Default")
      (node (ref "32U4") (pin "13") (pinfunction "/RESET_13") (pintype "bidirectional"))
      (node (ref "C11") (pin "1") (pinfunction "1_1") (pintype "passive"))
      (node (ref "CON_ISP") (pin "RESET") (pinfunction "RESET_RESET") (pintype "passive"))
      (node (ref "RK6") (pin "1") (pinfunction "1_1") (pintype "passive"))
      (node (ref "SJ1") (pin "2") (pinfunction "2_2") (pintype "passive"))
    )
    (net (code "33") (name "/RX") (class "Default")
      (node (ref "32U4") (pin "20") (pinfunction "PD2(INT2/RXD1)_20") (pintype "bidirectional"))
      (node (ref "U100") (pin "P$6") (pinfunction "P$6_P$6") (pintype "bidirectional"))
    )
    (net (code "34") (name "/RXLED") (class "Default")
      (node (ref "32U4") (pin "8") (pinfunction "PB0(SS)_8") (pintype "bidirectional"))
      (node (ref "RXLD") (pin "C") (pinfunction "C_C") (pintype "passive"))
    )
    (net (code "35") (name "/SCK") (class "Default")
      (node (ref "32U4") (pin "9") (pinfunction "PB1(SCK)_9") (pintype "bidirectional"))
      (node (ref "CON_ISP") (pin "SCK") (pinfunction "SCK_SCK") (pintype "passive"))
      (node (ref "RK3") (pin "1") (pinfunction "1_1") (pintype "passive"))
      (node (ref "X3") (pin "3") (pinfunction "1_3") (pintype "passive"))
    )
    (net (code "36") (name "/SCL") (class "Default")
      (node (ref "32U4") (pin "18") (pinfunction "PD0(INT0/OC0B/SCL)_18") (pintype "bidirectional"))
      (node (ref "J1") (pin "SCL") (pinfunction "2_SCL") (pintype "bidirectional"))
      (node (ref "J2") (pin "SCL") (pinfunction "2_SCL") (pintype "bidirectional"))
      (node (ref "RK2") (pin "2") (pinfunction "2_2") (pintype "passive"))
    )
    (net (code "37") (name "/SDA") (class "Default")
      (node (ref "32U4") (pin "19") (pinfunction "PD1(INT1/SDA)_19") (pintype "bidirectional"))
      (node (ref "J1") (pin "SDA") (pinfunction "3_SDA") (pintype "bidirectional"))
      (node (ref "J2") (pin "SDA") (pinfunction "3_SDA") (pintype "bidirectional"))
      (node (ref "RK1") (pin "2") (pinfunction "2_2") (pintype "passive"))
    )
    (net (code "38") (name "/TX") (class "Default")
      (node (ref "32U4") (pin "21") (pinfunction "PD3(INT3/TXD1)_21") (pintype "bidirectional"))
      (node (ref "U100") (pin "P$7") (pinfunction "P$7_P$7") (pintype "bidirectional"))
    )
    (net (code "39") (name "/TXLED") (class "Default")
      (node (ref "32U4") (pin "22") (pinfunction "PD5(XCK/CTS)_22") (pintype "bidirectional"))
      (node (ref "RXLD1") (pin "C") (pinfunction "C_C") (pintype "passive"))
    )
    (net (code "40") (name "/USB_N") (class "Default")
      (node (ref "32U4") (pin "3") (pinfunction "D-_3") (pintype "bidirectional"))
      (node (ref "RUSB1") (pin "1") (pinfunction "1_1") (pintype "passive"))
    )
    (net (code "41") (name "/USB_P") (class "Default")
      (node (ref "32U4") (pin "4") (pinfunction "D+_4") (pintype "bidirectional"))
      (node (ref "RUSB2") (pin "1") (pinfunction "1_1") (pintype "passive"))
    )
    (net (code "42") (name "/XTAL1") (class "Default")
      (node (ref "32U4") (pin "16") (pinfunction "XTAL2_16") (pintype "bidirectional"))
      (node (ref "CX2") (pin "2") (pinfunction "2_2") (pintype "passive"))
      (node (ref "RXT") (pin "1") (pinfunction "1_1") (pintype "passive"))
      (node (ref "X2") (pin "P$1") (pinfunction "P$1_P$1") (pintype "bidirectional"))
    )
    (net (code "43") (name "3.3V") (class "Default")
      (node (ref "100K") (pin "1") (pinfunction "1_1") (pintype "passive"))
      (node (ref "32U4") (pin "14") (pinfunction "VCC_14") (pintype "bidirectional"))
      (node (ref "32U4") (pin "2") (pinfunction "UVCC_2") (pintype "bidirectional"))
      (node (ref "32U4") (pin "24") (pinfunction "AVCC_24") (pintype "bidirectional"))
      (node (ref "32U4") (pin "34") (pinfunction "VCC1_34") (pintype "bidirectional"))
      (node (ref "32U4") (pin "44") (pinfunction "AVCC1_44") (pintype "bidirectional"))
      (node (ref "3V3") (pin "1") (pinfunction "1_1") (pintype "passive"))
      (node (ref "BJ1") (pin "2") (pinfunction "E_2") (pintype "passive"))
      (node (ref "C12") (pin "2") (pinfunction "2_2") (pintype "passive"))
      (node (ref "C14") (pin "1") (pinfunction "1_1") (pintype "passive"))
      (node (ref "C20") (pin "1") (pinfunction "1_1") (pintype "passive"))
      (node (ref "C23") (pin "1") (pinfunction "1_1") (pintype "passive"))
      (node (ref "C3") (pin "1") (pinfunction "1_1") (pintype "passive"))
      (node (ref "C32") (pin "1") (pinfunction "1_1") (pintype "passive"))
      (node (ref "C4") (pin "1") (pinfunction "1_1") (pintype "passive"))
      (node (ref "C43") (pin "1") (pinfunction "1_1") (pintype "passive"))
      (node (ref "C5") (pin "2") (pinfunction "2_2") (pintype "passive"))
      (node (ref "C6") (pin "1") (pinfunction "1_1") (pintype "passive"))
      (node (ref "CU1") (pin "1") (pinfunction "1_1") (pintype "passive"))
      (node (ref "CU8") (pin "1") (pinfunction "1_1") (pintype "passive"))
      (node (ref "IC1") (pin "3") (pinfunction "VO_3") (pintype "passive"))
      (node (ref "IC2") (pin "4") (pinfunction "V+_4") (pintype "power_in"))
      (node (ref "IC3") (pin "4") (pinfunction "V+_4") (pintype "power_in"))
      (node (ref "IC4") (pin "10") (pinfunction "VCC_10") (pintype "bidirectional"))
      (node (ref "IC5") (pin "2") (pinfunction "IN_2") (pintype "input"))
      (node (ref "IC6") (pin "10") (pinfunction "VCC_10") (pintype "bidirectional"))
      (node (ref "R14") (pin "1") (pinfunction "1_1") (pintype "passive"))
      (node (ref "R29") (pin "2") (pinfunction "2_2") (pintype "passive"))
      (node (ref "R30") (pin "2") (pinfunction "2_2") (pintype "passive"))
      (node (ref "R31") (pin "2") (pinfunction "2_2") (pintype "passive"))
      (node (ref "R32") (pin "2") (pinfunction "2_2") (pintype "passive"))
      (node (ref "R33") (pin "2") (pinfunction "2_2") (pintype "passive"))
      (node (ref "R34") (pin "2") (pinfunction "2_2") (pintype "passive"))
      (node (ref "R39") (pin "2") (pinfunction "2_2") (pintype "passive"))
      (node (ref "R43") (pin "2") (pinfunction "2_2") (pintype "passive"))
      (node (ref "R44") (pin "2") (pinfunction "2_2") (pintype "passive"))
      (node (ref "R45") (pin "2") (pinfunction "2_2") (pintype "passive"))
      (node (ref "R47") (pin "2") (pinfunction "2_2") (pintype "passive"))
      (node (ref "R48") (pin "2") (pinfunction "2_2") (pintype "passive"))
      (node (ref "R6") (pin "2") (pinfunction "2_2") (pintype "passive"))
      (node (ref "RK1") (pin "1") (pinfunction "1_1") (pintype "passive"))
      (node (ref "RK15") (pin "1") (pinfunction "1_1") (pintype "passive"))
      (node (ref "RK16") (pin "1") (pinfunction "1_1") (pintype "passive"))
      (node (ref "RK18") (pin "1") (pinfunction "1_1") (pintype "passive"))
      (node (ref "RK19") (pin "1") (pinfunction "1_1") (pintype "passive"))
      (node (ref "RK2") (pin "1") (pinfunction "1_1") (pintype "passive"))
      (node (ref "RK4") (pin "2") (pinfunction "2_2") (pintype "passive"))
      (node (ref "RK5") (pin "2") (pinfunction "2_2") (pintype "passive"))
      (node (ref "RK6") (pin "2") (pinfunction "2_2") (pintype "passive"))
      (node (ref "U$1") (pin "RST/HOLD") (pinfunction "HOLD_RST/HOLD") (pintype "bidirectional"))
      (node (ref "U$1") (pin "VDD") (pinfunction "VCC_VDD") (pintype "bidirectional"))
      (node (ref "U$1") (pin "WP") (pinfunction "WP_WP") (pintype "bidirectional"))
      (node (ref "U$3") (pin "P$1") (pinfunction "1_P$1") (pintype "passive"))
      (node (ref "U1") (pin "1") (pinfunction "VSUP_1") (pintype "bidirectional"))
      (node (ref "U1") (pin "16") (pinfunction "DVDD_16") (pintype "bidirectional"))
      (node (ref "U100") (pin "P$12") (pinfunction "P$12_P$12") (pintype "bidirectional"))
      (node (ref "U100") (pin "P$34") (pinfunction "P$34_P$34") (pintype "bidirectional"))
    )
    (net (code "44") (name "GND") (class "Default")
      (node (ref "32U4") (pin "15") (pinfunction "GND_15") (pintype "bidirectional"))
      (node (ref "32U4") (pin "23") (pinfunction "GND1_23") (pintype "bidirectional"))
      (node (ref "32U4") (pin "35") (pinfunction "GND2_35") (pintype "bidirectional"))
      (node (ref "32U4") (pin "43") (pinfunction "GND3_43") (pintype "bidirectional"))
      (node (ref "32U4") (pin "5") (pinfunction "UGND_5") (pintype "bidirectional"))
      (node (ref "BKLD") (pin "C") (pinfunction "C_C") (pintype "passive"))
      (node (ref "C1") (pin "2") (pinfunction "2_2") (pintype "passive"))
      (node (ref "C10") (pin "2") (pinfunction "2_2") (pintype "passive"))
      (node (ref "C11") (pin "2") (pinfunction "2_2") (pintype "passive"))
      (node (ref "C12") (pin "1") (pinfunction "1_1") (pintype "passive"))
      (node (ref "C13") (pin "1") (pinfunction "1_1") (pintype "passive"))
      (node (ref "C14") (pin "2") (pinfunction "2_2") (pintype "passive"))
      (node (ref "C15") (pin "1") (pinfunction "1_1") (pintype "passive"))
      (node (ref "C16") (pin "1") (pinfunction "1_1") (pintype "passive"))
      (node (ref "C17") (pin "1") (pinfunction "1_1") (pintype "passive"))
      (node (ref "C2") (pin "2") (pinfunction "2_2") (pintype "passive"))
      (node (ref "C20") (pin "2") (pinfunction "2_2") (pintype "passive"))
      (node (ref "C22") (pin "1") (pinfunction "1_1") (pintype "passive"))
      (node (ref "C23") (pin "2") (pinfunction "2_2") (pintype "passive"))
      (node (ref "C25") (pin "2") (pinfunction "2_2") (pintype "passive"))
      (node (ref "C26") (pin "2") (pinfunction "2_2") (pintype "passive"))
      (node (ref "C27") (pin "2") (pinfunction "2_2") (pintype "passive"))
      (node (ref "C28") (pin "2") (pinfunction "2_2") (pintype "passive"))
      (node (ref "C29") (pin "2") (pinfunction "2_2") (pintype "passive"))
      (node (ref "C30") (pin "2") (pinfunction "2_2") (pintype "passive"))
      (node (ref "C31") (pin "2") (pinfunction "2_2") (pintype "passive"))
      (node (ref "C32") (pin "2") (pinfunction "2_2") (pintype "passive"))
      (node (ref "C33") (pin "2") (pinfunction "2_2") (pintype "passive"))
      (node (ref "C36") (pin "2") (pinfunction "2_2") (pintype "passive"))
      (node (ref "C37") (pin "2") (pinfunction "2_2") (pintype "passive"))
      (node (ref "C38") (pin "2") (pinfunction "2_2") (pintype "passive"))
      (node (ref "C39") (pin "2") (pinfunction "2_2") (pintype "passive"))
      (node (ref "C40") (pin "2") (pinfunction "2_2") (pintype "passive"))
      (node (ref "C41") (pin "2") (pinfunction "2_2") (pintype "passive"))
      (node (ref "C42") (pin "2") (pinfunction "2_2") (pintype "passive"))
      (node (ref "C43") (pin "2") (pinfunction "2_2") (pintype "passive"))
      (node (ref "C44") (pin "2") (pinfunction "2_2") (pintype "passive"))
      (node (ref "C47") (pin "-") (pinfunction "-_-") (pintype "passive"))
      (node (ref "C48") (pin "-") (pinfunction "-_-") (pintype "passive"))
      (node (ref "C5") (pin "1") (pinfunction "1_1") (pintype "passive"))
      (node (ref "C6") (pin "2") (pinfunction "2_2") (pintype "passive"))
      (node (ref "CON1") (pin "P$2") (pinfunction "GND_P$2") (pintype "bidirectional"))
      (node (ref "CON_ISP") (pin "GND") (pinfunction "GND_GND") (pintype "passive"))
      (node (ref "CU1") (pin "2") (pinfunction "2_2") (pintype "passive"))
      (node (ref "CU3") (pin "2") (pinfunction "2_2") (pintype "passive"))
      (node (ref "CU4") (pin "2") (pinfunction "2_2") (pintype "passive"))
      (node (ref "CU7") (pin "2") (pinfunction "2_2") (pintype "passive"))
      (node (ref "CU8") (pin "2") (pinfunction "2_2") (pintype "passive"))
      (node (ref "CU9") (pin "1") (pinfunction "1_1") (pintype "passive"))
      (node (ref "CX1") (pin "1") (pinfunction "1_1") (pintype "passive"))
      (node (ref "CX2") (pin "1") (pinfunction "1_1") (pintype "passive"))
      (node (ref "GND") (pin "1") (pinfunction "1_1") (pintype "passive"))
      (node (ref "IC1") (pin "2") (pinfunction "GND_2") (pintype "passive"))
      (node (ref "IC2") (pin "11") (pinfunction "V-_11") (pintype "power_in"))
      (node (ref "IC4") (pin "21") (pinfunction "GND1_21") (pintype "bidirectional"))
      (node (ref "IC4") (pin "7") (pinfunction "GND_7") (pintype "bidirectional"))
      (node (ref "IC4") (pin "P$1") (pinfunction "GND2_P$1") (pintype "bidirectional"))
      (node (ref "IC5") (pin "4") (pinfunction "GND_4") (pintype "passive"))
      (node (ref "IC6") (pin "21") (pinfunction "GND1_21") (pintype "bidirectional"))
      (node (ref "IC6") (pin "7") (pinfunction "GND_7") (pintype "bidirectional"))
      (node (ref "IC6") (pin "P$1") (pinfunction "GND2_P$1") (pintype "bidirectional"))
      (node (ref "J1") (pin "GND1") (pinfunction "6_GND1") (pintype "bidirectional"))
      (node (ref "J1") (pin "GND2") (pinfunction "4_GND2") (pintype "bidirectional"))
      (node (ref "J2") (pin "GND1") (pinfunction "6_GND1") (pintype "bidirectional"))
      (node (ref "J2") (pin "GND2") (pinfunction "4_GND2") (pintype "bidirectional"))
      (node (ref "LDPW12") (pin "C") (pinfunction "C_C") (pintype "passive"))
      (node (ref "LDPW3") (pin "C") (pinfunction "C_C") (pintype "passive"))
      (node (ref "R11") (pin "1") (pinfunction "1_1") (pintype "passive"))
      (node (ref "R16") (pin "2") (pinfunction "2_2") (pintype "passive"))
      (node (ref "R19") (pin "2") (pinfunction "2_2") (pintype "passive"))
      (node (ref "R20") (pin "1") (pinfunction "1_1") (pintype "passive"))
      (node (ref "R21") (pin "2") (pinfunction "2_2") (pintype "passive"))
      (node (ref "R25") (pin "1") (pinfunction "1_1") (pintype "passive"))
      (node (ref "R26") (pin "1") (pinfunction "1_1") (pintype "passive"))
      (node (ref "R27") (pin "1") (pinfunction "1_1") (pintype "passive"))
      (node (ref "R28") (pin "1") (pinfunction "1_1") (pintype "passive"))
      (node (ref "R35") (pin "1") (pinfunction "1_1") (pintype "passive"))
      (node (ref "R36") (pin "1") (pinfunction "1_1") (pintype "passive"))
      (node (ref "R37") (pin "1") (pinfunction "1_1") (pintype "passive"))
      (node (ref "R38") (pin "1") (pinfunction "1_1") (pintype "passive"))
      (node (ref "R40") (pin "1") (pinfunction "1_1") (pintype "passive"))
      (node (ref "R41") (pin "1") (pinfunction "1_1") (pintype "passive"))
      (node (ref "R42") (pin "1") (pinfunction "1_1") (pintype "passive"))
      (node (ref "R46") (pin "1") (pinfunction "1_1") (pintype "passive"))
      (node (ref "R49") (pin "1") (pinfunction "1_1") (pintype "passive"))
      (node (ref "R5") (pin "1") (pinfunction "1_1") (pintype "passive"))
      (node (ref "R50") (pin "1") (pinfunction "1_1") (pintype "passive"))
      (node (ref "R51") (pin "1") (pinfunction "1_1") (pintype "passive"))
      (node (ref "R52") (pin "1") (pinfunction "1_1") (pintype "passive"))
      (node (ref "R7") (pin "1") (pinfunction "1_1") (pintype "passive"))
      (node (ref "R8") (pin "1") (pinfunction "1_1") (pintype "passive"))
      (node (ref "RK7") (pin "1") (pinfunction "1_1") (pintype "passive"))
      (node (ref "SJ1") (pin "1") (pinfunction "1_1") (pintype "passive"))
      (node (ref "SJ2") (pin "1") (pinfunction "1_1") (pintype "passive"))
      (node (ref "SJ3") (pin "2") (pinfunction "2_2") (pintype "passive"))
      (node (ref "SJ4") (pin "1") (pinfunction "1_1") (pintype "passive"))
      (node (ref "SJ5") (pin "1") (pinfunction "1_1") (pintype "passive"))
      (node (ref "SJ6") (pin "1") (pinfunction "1_1") (pintype "passive"))
      (node (ref "SJ7") (pin "1") (pinfunction "1_1") (pintype "passive"))
      (node (ref "SJ8") (pin "1") (pinfunction "1_1") (pintype "passive"))
      (node (ref "SJ9") (pin "1") (pinfunction "1_1") (pintype "passive"))
      (node (ref "U$1") (pin "VSS") (pinfunction "GND_VSS") (pintype "bidirectional"))
      (node (ref "U$5") (pin "G") (pinfunction "GND_G") (pintype "bidirectional"))
      (node (ref "U1") (pin "14") (pinfunction "XI_14") (pintype "bidirectional"))
      (node (ref "X3") (pin "7") (pinfunction "1_7") (pintype "passive"))
      (node (ref "X3") (pin "8") (pinfunction "1_8") (pintype "passive"))
      (node (ref "X4") (pin "5") (pinfunction "5_5") (pintype "passive"))
    )
    (net (code "45") (name "Net-(32U4-UCAP)") (class "Default")
      (node (ref "32U4") (pin "6") (pinfunction "UCAP_6") (pintype "bidirectional"))
      (node (ref "C13") (pin "2") (pinfunction "2_2") (pintype "passive"))
    )
    (net (code "46") (name "Net-(B1-AC1)") (class "Default")
      (node (ref "B1") (pin "~1") (pinfunction "AC1_~1") (pintype "passive"))
      (node (ref "IC3") (pin "9") (pinfunction "-IN_9") (pintype "input"))
      (node (ref "R21") (pin "1") (pinfunction "1_1") (pintype "passive"))
    )
    (net (code "47") (name "Net-(B1-AC2)") (class "Default")
      (node (ref "B1") (pin "~2") (pinfunction "AC2_~2") (pintype "passive"))
      (node (ref "IC3") (pin "8") (pinfunction "OUT_8") (pintype "output"))
    )
    (net (code "48") (name "Net-(B1-Pad+)") (class "Default")
      (node (ref "B1") (pin "+") (pinfunction "+_+") (pintype "passive"))
      (node (ref "C18") (pin "2") (pinfunction "2_2") (pintype "passive"))
      (node (ref "R17") (pin "2") (pinfunction "2_2") (pintype "passive"))
      (node (ref "R22") (pin "1") (pinfunction "1_1") (pintype "passive"))
    )
    (net (code "49") (name "Net-(B1-Pad-)") (class "Default")
      (node (ref "B1") (pin "-") (pinfunction "-_-") (pintype "passive"))
      (node (ref "C18") (pin "1") (pinfunction "1_1") (pintype "passive"))
      (node (ref "R17") (pin "1") (pinfunction "1_1") (pintype "passive"))
      (node (ref "R23") (pin "1") (pinfunction "1_1") (pintype "passive"))
    )
    (net (code "50") (name "Net-(BJ1-B)") (class "Default")
      (node (ref "BJ1") (pin "1") (pinfunction "B_1") (pintype "passive"))
      (node (ref "U1") (pin "2") (pinfunction "BASE_2") (pintype "bidirectional"))
    )
    (net (code "51") (name "Net-(BJ1-C)") (class "Default")
      (node (ref "20K") (pin "2") (pinfunction "2_2") (pintype "passive"))
      (node (ref "BJ1") (pin "3") (pinfunction "C_3") (pintype "passive"))
      (node (ref "C7") (pin "1") (pinfunction "1_1") (pintype "passive"))
      (node (ref "CU2") (pin "1") (pinfunction "1_1") (pintype "passive"))
      (node (ref "U1") (pin "3") (pinfunction "AVDD_3") (pintype "bidirectional"))
    )
    (net (code "52") (name "Net-(BKLD-PadA)") (class "Default")
      (node (ref "BKLD") (pin "A") (pinfunction "A_A") (pintype "passive"))
      (node (ref "R2") (pin "2") (pinfunction "2_2") (pintype "passive"))
    )
    (net (code "53") (name "Net-(C9-Pad1)") (class "Default")
      (node (ref "C9") (pin "1") (pinfunction "1_1") (pintype "passive"))
      (node (ref "R13") (pin "1") (pinfunction "1_1") (pintype "passive"))
    )
    (net (code "54") (name "Net-(C19-Pad2)") (class "Default")
      (node (ref "C19") (pin "2") (pinfunction "2_2") (pintype "passive"))
      (node (ref "D3") (pin "C") (pinfunction "C_C") (pintype "passive"))
      (node (ref "D5") (pin "A") (pinfunction "A_A") (pintype "passive"))
    )
    (net (code "55") (name "Net-(IC2A--IN)") (class "Default")
      (node (ref "C15") (pin "2") (pinfunction "2_2") (pintype "passive"))
      (node (ref "IC2") (pin "2") (pinfunction "-IN_2") (pintype "input"))
      (node (ref "R6") (pin "1") (pinfunction "1_1") (pintype "passive"))
      (node (ref "R8") (pin "2") (pinfunction "2_2") (pintype "passive"))
    )
    (net (code "56") (name "Net-(IC2B-+IN)") (class "Default")
      (node (ref "IC2") (pin "5") (pinfunction "+IN_5") (pintype "input"))
      (node (ref "U$2") (pin "S") (pinfunction "OUT_S") (pintype "bidirectional"))
    )
    (net (code "57") (name "Net-(IC2B--IN)") (class "Default")
      (node (ref "IC2") (pin "6") (pinfunction "-IN_6") (pintype "input"))
      (node (ref "IC2") (pin "7") (pinfunction "OUT_7") (pintype "output"))
      (node (ref "R4") (pin "1") (pinfunction "1_1") (pintype "passive"))
    )
    (net (code "58") (name "Net-(IC3A-+IN)") (class "Default")
      (node (ref "C17") (pin "2") (pinfunction "2_2") (pintype "passive"))
      (node (ref "C9") (pin "2") (pinfunction "2_2") (pintype "passive"))
      (node (ref "IC3") (pin "3") (pinfunction "+IN_3") (pintype "input"))
      (node (ref "R11") (pin "2") (pinfunction "2_2") (pintype "passive"))
    )
    (net (code "59") (name "Net-(IC3A--IN)") (class "Default")
      (node (ref "D3") (pin "A") (pinfunction "A_A") (pintype "passive"))
      (node (ref "D5") (pin "C") (pinfunction "C_C") (pintype "passive"))
      (node (ref "IC3") (pin "2") (pinfunction "-IN_2") (pintype "input"))
      (node (ref "R10") (pin "1") (pinfunction "1_1") (pintype "passive"))
      (node (ref "R7") (pin "2") (pinfunction "2_2") (pintype "passive"))
    )
    (net (code "60") (name "Net-(IC3A-OUT)") (class "Default")
      (node (ref "C19") (pin "1") (pinfunction "1_1") (pintype "passive"))
      (node (ref "IC3") (pin "1") (pinfunction "OUT_1") (pintype "output"))
      (node (ref "R10") (pin "2") (pinfunction "2_2") (pintype "passive"))
      (node (ref "R13") (pin "2") (pinfunction "2_2") (pintype "passive"))
      (node (ref "R15") (pin "1") (pinfunction "1_1") (pintype "passive"))
    )
    (net (code "61") (name "Net-(IC3B-+IN)") (class "Default")
      (node (ref "IC3") (pin "5") (pinfunction "+IN_5") (pintype "input"))
      (node (ref "R15") (pin "2") (pinfunction "2_2") (pintype "passive"))
      (node (ref "R16") (pin "1") (pinfunction "1_1") (pintype "passive"))
      (node (ref "TP5") (pin "P$1") (pinfunction "1_P$1") (pintype "bidirectional"))
    )
    (net (code "62") (name "Net-(IC3B--IN)") (class "Default")
      (node (ref "IC3") (pin "6") (pinfunction "-IN_6") (pintype "input"))
      (node (ref "R18") (pin "1") (pinfunction "1_1") (pintype "passive"))
      (node (ref "U$5") (pin "S") (pinfunction "OUT_S") (pintype "bidirectional"))
    )
    (net (code "63") (name "Net-(IC3B-OUT)") (class "Default")
      (node (ref "C24") (pin "1") (pinfunction "1_1") (pintype "passive"))
      (node (ref "IC3") (pin "7") (pinfunction "OUT_7") (pintype "output"))
      (node (ref "R18") (pin "2") (pinfunction "2_2") (pintype "passive"))
    )
    (net (code "64") (name "Net-(IC3C-+IN)") (class "Default")
      (node (ref "C24") (pin "2") (pinfunction "2_2") (pintype "passive"))
      (node (ref "IC3") (pin "10") (pinfunction "+IN_10") (pintype "input"))
      (node (ref "R20") (pin "2") (pinfunction "2_2") (pintype "passive"))
    )
    (net (code "65") (name "Net-(IC3D-+IN)") (class "Default")
      (node (ref "IC3") (pin "12") (pinfunction "+IN_12") (pintype "input"))
      (node (ref "R22") (pin "2") (pinfunction "2_2") (pintype "passive"))
    )
    (net (code "66") (name "Net-(IC3D--IN)") (class "Default")
      (node (ref "IC3") (pin "13") (pinfunction "-IN_13") (pintype "input"))
      (node (ref "R23") (pin "2") (pinfunction "2_2") (pintype "passive"))
      (node (ref "R24") (pin "2") (pinfunction "2_2") (pintype "passive"))
    )
    (net (code "67") (name "Net-(IC4-AOUT1)") (class "Default")
      (node (ref "IC4") (pin "4") (pinfunction "AOUT1_4") (pintype "bidirectional"))
      (node (ref "JP1") (pin "1") (pinfunction "1_1") (pintype "passive"))
    )
    (net (code "68") (name "Net-(IC4-AOUT2)") (class "Default")
      (node (ref "IC4") (pin "25") (pinfunction "AOUT2_25") (pintype "bidirectional"))
      (node (ref "JP1") (pin "2") (pinfunction "2_2") (pintype "passive"))
    )
    (net (code "69") (name "Net-(IC4-BOUT1)") (class "Default")
      (node (ref "IC4") (pin "11") (pinfunction "BOUT1_11") (pintype "bidirectional"))
      (node (ref "JP1") (pin "3") (pinfunction "3_3") (pintype "passive"))
    )
    (net (code "70") (name "Net-(IC4-BOUT2)") (class "Default")
      (node (ref "IC4") (pin "18") (pinfunction "BOUT2_18") (pintype "bidirectional"))
      (node (ref "JP1") (pin "4") (pinfunction "4_4") (pintype "passive"))
    )
    (net (code "71") (name "Net-(IC4-CP1)") (class "Default")
      (node (ref "C35") (pin "1") (pinfunction "1_1") (pintype "passive"))
      (node (ref "IC4") (pin "23") (pinfunction "CP1_23") (pintype "bidirectional"))
    )
    (net (code "72") (name "Net-(IC4-CP2)") (class "Default")
      (node (ref "C35") (pin "2") (pinfunction "2_2") (pintype "passive"))
      (node (ref "IC4") (pin "24") (pinfunction "CP2_24") (pintype "bidirectional"))
    )
    (net (code "73") (name "Net-(IC4-DECAY)") (class "Default")
      (node (ref "C28") (pin "1") (pinfunction "1_1") (pintype "passive"))
      (node (ref "IC4") (pin "5") (pinfunction "DECAY_5") (pintype "bidirectional"))
      (node (ref "R30") (pin "1") (pinfunction "1_1") (pintype "passive"))
      (node (ref "R37") (pin "2") (pinfunction "2_2") (pintype "passive"))
    )
    (net (code "74") (name "Net-(IC4-ENABLE)") (class "Default")
      (node (ref "IC4") (pin "26") (pinfunction "ENABLE_26") (pintype "bidirectional"))
      (node (ref "R35") (pin "2") (pinfunction "2_2") (pintype "passive"))
    )
    (net (code "75") (name "Net-(IC4-ISENA)") (class "Default")
      (node (ref "C31") (pin "1") (pinfunction "1_1") (pintype "passive"))
      (node (ref "IC4") (pin "1") (pinfunction "ISENA_1") (pintype "bidirectional"))
      (node (ref "R38") (pin "2") (pinfunction "2_2") (pintype "passive"))
    )
    (net (code "76") (name "Net-(IC4-ISENB)") (class "Default")
      (node (ref "C30") (pin "1") (pinfunction "1_1") (pintype "passive"))
      (node (ref "IC4") (pin "14") (pinfunction "ISENB_14") (pintype "bidirectional"))
      (node (ref "R26") (pin "2") (pinfunction "2_2") (pintype "passive"))
    )
    (net (code "77") (name "Net-(IC4-RCA)") (class "Default")
      (node (ref "C25") (pin "1") (pinfunction "1_1") (pintype "passive"))
      (node (ref "IC4") (pin "6") (pinfunction "RCA_6") (pintype "bidirectional"))
      (node (ref "R25") (pin "2") (pinfunction "2_2") (pintype "passive"))
    )
    (net (code "78") (name "Net-(IC4-RCB)") (class "Default")
      (node (ref "C26") (pin "1") (pinfunction "1_1") (pintype "passive"))
      (node (ref "IC4") (pin "9") (pinfunction "RCB_9") (pintype "bidirectional"))
      (node (ref "R27") (pin "2") (pinfunction "2_2") (pintype "passive"))
    )
    (net (code "79") (name "Net-(IC4-RESET)") (class "Default")
      (node (ref "IC4") (pin "17") (pinfunction "RESET_17") (pintype "bidirectional"))
      (node (ref "R33") (pin "1") (pinfunction "1_1") (pintype "passive"))
    )
    (net (code "80") (name "Net-(IC4-SLEEP)") (class "Default")
      (node (ref "IC4") (pin "27") (pinfunction "SLEEP_27") (pintype "bidirectional"))
      (node (ref "R34") (pin "1") (pinfunction "1_1") (pintype "passive"))
    )
    (net (code "81") (name "Net-(IC4-SR)") (class "Default")
      (node (ref "IC4") (pin "16") (pinfunction "SR_16") (pintype "bidirectional"))
      (node (ref "R36") (pin "2") (pinfunction "2_2") (pintype "passive"))
    )
    (net (code "82") (name "Net-(IC4-USM0)") (class "Default")
      (node (ref "IC4") (pin "13") (pinfunction "USM0_13") (pintype "bidirectional"))
      (node (ref "R32") (pin "1") (pinfunction "1_1") (pintype "passive"))
      (node (ref "SJ7") (pin "2") (pinfunction "2_2") (pintype "passive"))
    )
    (net (code "83") (name "Net-(IC4-USM1)") (class "Default")
      (node (ref "IC4") (pin "12") (pinfunction "USM1_12") (pintype "bidirectional"))
      (node (ref "R31") (pin "1") (pinfunction "1_1") (pintype "passive"))
      (node (ref "SJ5") (pin "2") (pinfunction "2_2") (pintype "passive"))
    )
    (net (code "84") (name "Net-(IC4-VCP)") (class "Default")
      (node (ref "C34") (pin "2") (pinfunction "2_2") (pintype "passive"))
      (node (ref "IC4") (pin "22") (pinfunction "VCP_22") (pintype "bidirectional"))
    )
    (net (code "85") (name "Net-(IC4-VGD)") (class "Default")
      (node (ref "C29") (pin "1") (pinfunction "1_1") (pintype "passive"))
      (node (ref "IC4") (pin "20") (pinfunction "VGD_20") (pintype "bidirectional"))
    )
    (net (code "86") (name "Net-(IC4-VREF)") (class "Default")
      (node (ref "C27") (pin "1") (pinfunction "1_1") (pintype "passive"))
      (node (ref "IC4") (pin "8") (pinfunction "VREF_8") (pintype "bidirectional"))
      (node (ref "R28") (pin "2") (pinfunction "2_2") (pintype "passive"))
      (node (ref "R29") (pin "1") (pinfunction "1_1") (pintype "passive"))
    )
    (net (code "87") (name "Net-(IC5-CFLY+)") (class "Default")
      (node (ref "C21") (pin "2") (pinfunction "2_2") (pintype "passive"))
      (node (ref "IC5") (pin "5") (pinfunction "CFLY+_5") (pintype "passive"))
    )
    (net (code "88") (name "Net-(IC5-CFLY-)") (class "Default")
      (node (ref "C21") (pin "1") (pinfunction "1_1") (pintype "passive"))
      (node (ref "IC5") (pin "3") (pinfunction "CFLY-_3") (pintype "power_in"))
    )
    (net (code "89") (name "Net-(IC6-AOUT1)") (class "Default")
      (node (ref "IC6") (pin "4") (pinfunction "AOUT1_4") (pintype "bidirectional"))
      (node (ref "JP3") (pin "1") (pinfunction "1_1") (pintype "passive"))
    )
    (net (code "90") (name "Net-(IC6-AOUT2)") (class "Default")
      (node (ref "IC6") (pin "25") (pinfunction "AOUT2_25") (pintype "bidirectional"))
      (node (ref "JP3") (pin "2") (pinfunction "2_2") (pintype "passive"))
    )
    (net (code "91") (name "Net-(IC6-BOUT1)") (class "Default")
      (node (ref "IC6") (pin "11") (pinfunction "BOUT1_11") (pintype "bidirectional"))
      (node (ref "JP3") (pin "3") (pinfunction "3_3") (pintype "passive"))
    )
    (net (code "92") (name "Net-(IC6-BOUT2)") (class "Default")
      (node (ref "IC6") (pin "18") (pinfunction "BOUT2_18") (pintype "bidirectional"))
      (node (ref "JP3") (pin "4") (pinfunction "4_4") (pintype "passive"))
    )
    (net (code "93") (name "Net-(IC6-CP1)") (class "Default")
      (node (ref "C46") (pin "1") (pinfunction "1_1") (pintype "passive"))
      (node (ref "IC6") (pin "23") (pinfunction "CP1_23") (pintype "bidirectional"))
    )
    (net (code "94") (name "Net-(IC6-CP2)") (class "Default")
      (node (ref "C46") (pin "2") (pinfunction "2_2") (pintype "passive"))
      (node (ref "IC6") (pin "24") (pinfunction "CP2_24") (pintype "bidirectional"))
    )
    (net (code "95") (name "Net-(IC6-DECAY)") (class "Default")
      (node (ref "C39") (pin "1") (pinfunction "1_1") (pintype "passive"))
      (node (ref "IC6") (pin "5") (pinfunction "DECAY_5") (pintype "bidirectional"))
      (node (ref "R43") (pin "1") (pinfunction "1_1") (pintype "passive"))
      (node (ref "R51") (pin "2") (pinfunction "2_2") (pintype "passive"))
    )
    (net (code "96") (name "Net-(IC6-ENABLE)") (class "Default")
      (node (ref "IC6") (pin "26") (pinfunction "ENABLE_26") (pintype "bidirectional"))
      (node (ref "R49") (pin "2") (pinfunction "2_2") (pintype "passive"))
    )
    (net (code "97") (name "Net-(IC6-ISENA)") (class "Default")
      (node (ref "C42") (pin "1") (pinfunction "1_1") (pintype "passive"))
      (node (ref "IC6") (pin "1") (pinfunction "ISENA_1") (pintype "bidirectional"))
      (node (ref "R52") (pin "2") (pinfunction "2_2") (pintype "passive"))
    )
    (net (code "98") (name "Net-(IC6-ISENB)") (class "Default")
      (node (ref "C41") (pin "1") (pinfunction "1_1") (pintype "passive"))
      (node (ref "IC6") (pin "14") (pinfunction "ISENB_14") (pintype "bidirectional"))
      (node (ref "R46") (pin "2") (pinfunction "2_2") (pintype "passive"))
    )
    (net (code "99") (name "Net-(IC6-RCA)") (class "Default")
      (node (ref "C36") (pin "1") (pinfunction "1_1") (pintype "passive"))
      (node (ref "IC6") (pin "6") (pinfunction "RCA_6") (pintype "bidirectional"))
      (node (ref "R40") (pin "2") (pinfunction "2_2") (pintype "passive"))
    )
    (net (code "100") (name "Net-(IC6-RCB)") (class "Default")
      (node (ref "C37") (pin "1") (pinfunction "1_1") (pintype "passive"))
      (node (ref "IC6") (pin "9") (pinfunction "RCB_9") (pintype "bidirectional"))
      (node (ref "R41") (pin "2") (pinfunction "2_2") (pintype "passive"))
    )
    (net (code "101") (name "Net-(IC6-RESET)") (class "Default")
      (node (ref "IC6") (pin "17") (pinfunction "RESET_17") (pintype "bidirectional"))
      (node (ref "R47") (pin "1") (pinfunction "1_1") (pintype "passive"))
    )
    (net (code "102") (name "Net-(IC6-SLEEP)") (class "Default")
      (node (ref "IC6") (pin "27") (pinfunction "SLEEP_27") (pintype "bidirectional"))
      (node (ref "R48") (pin "1") (pinfunction "1_1") (pintype "passive"))
    )
    (net (code "103") (name "Net-(IC6-SR)") (class "Default")
      (node (ref "IC6") (pin "16") (pinfunction "SR_16") (pintype "bidirectional"))
      (node (ref "R50") (pin "2") (pinfunction "2_2") (pintype "passive"))
    )
    (net (code "104") (name "Net-(IC6-USM0)") (class "Default")
      (node (ref "IC6") (pin "13") (pinfunction "USM0_13") (pintype "bidirectional"))
      (node (ref "R45") (pin "1") (pinfunction "1_1") (pintype "passive"))
      (node (ref "SJ9") (pin "2") (pinfunction "2_2") (pintype "passive"))
    )
    (net (code "105") (name "Net-(IC6-USM1)") (class "Default")
      (node (ref "IC6") (pin "12") (pinfunction "USM1_12") (pintype "bidirectional"))
      (node (ref "R44") (pin "1") (pinfunction "1_1") (pintype "passive"))
      (node (ref "SJ8") (pin "2") (pinfunction "2_2") (pintype "passive"))
    )
    (net (code "106") (name "Net-(IC6-VCP)") (class "Default")
      (node (ref "C45") (pin "2") (pinfunction "2_2") (pintype "passive"))
      (node (ref "IC6") (pin "22") (pinfunction "VCP_22") (pintype "bidirectional"))
    )
    (net (code "107") (name "Net-(IC6-VGD)") (class "Default")
      (node (ref "C40") (pin "1") (pinfunction "1_1") (pintype "passive"))
      (node (ref "IC6") (pin "20") (pinfunction "VGD_20") (pintype "bidirectional"))
    )
    (net (code "108") (name "Net-(IC6-VREF)") (class "Default")
      (node (ref "C38") (pin "1") (pinfunction "1_1") (pintype "passive"))
      (node (ref "IC6") (pin "8") (pinfunction "VREF_8") (pintype "bidirectional"))
      (node (ref "R39") (pin "1") (pinfunction "1_1") (pintype "passive"))
      (node (ref "R42") (pin "2") (pinfunction "2_2") (pintype "passive"))
    )
    (net (code "109") (name "Net-(LDMEM-PadA)") (class "Default")
      (node (ref "LDMEM") (pin "A") (pinfunction "A_A") (pintype "passive"))
      (node (ref "RK19") (pin "2") (pinfunction "2_2") (pintype "passive"))
    )
    (net (code "110") (name "Net-(LDPW3-PadA)") (class "Default")
      (node (ref "LDPW3") (pin "A") (pinfunction "A_A") (pintype "passive"))
      (node (ref "R14") (pin "2") (pinfunction "2_2") (pintype "passive"))
    )
    (net (code "111") (name "Net-(LDPW12-PadA)") (class "Default")
      (node (ref "LDPW12") (pin "A") (pinfunction "A_A") (pintype "passive"))
      (node (ref "R12") (pin "1") (pinfunction "1_1") (pintype "passive"))
    )
    (net (code "112") (name "Net-(LDSLAVE-PadA)") (class "Default")
      (node (ref "LDSLAVE") (pin "A") (pinfunction "A_A") (pintype "passive"))
      (node (ref "RK18") (pin "2") (pinfunction "2_2") (pintype "passive"))
    )
    (net (code "113") (name "Net-(R4-Pad2)") (class "Default")
      (node (ref "R4") (pin "2") (pinfunction "2_2") (pintype "passive"))
      (node (ref "R5") (pin "2") (pinfunction "2_2") (pintype "passive"))
      (node (ref "R9") (pin "1") (pinfunction "1_1") (pintype "passive"))
    )
    (net (code "114") (name "Net-(RK3-Pad2)") (class "Default")
      (node (ref "RK3") (pin "2") (pinfunction "2_2") (pintype "passive"))
      (node (ref "U$1") (pin "SCK") (pinfunction "SCK_SCK") (pintype "bidirectional"))
    )
    (net (code "115") (name "Net-(RK15-Pad2)") (class "Default")
      (node (ref "RK15") (pin "2") (pinfunction "2_2") (pintype "passive"))
      (node (ref "RXLD1") (pin "A") (pinfunction "A_A") (pintype "passive"))
    )
    (net (code "116") (name "Net-(RK16-Pad2)") (class "Default")
      (node (ref "RK16") (pin "2") (pinfunction "2_2") (pintype "passive"))
      (node (ref "RXLD") (pin "A") (pinfunction "A_A") (pintype "passive"))
    )
    (net (code "117") (name "Net-(RUSB1-Pad2)") (class "Default")
      (node (ref "RUSB1") (pin "2") (pinfunction "2_2") (pintype "passive"))
      (node (ref "X4") (pin "2") (pinfunction "2_2") (pintype "passive"))
    )
    (net (code "118") (name "Net-(RUSB2-Pad2)") (class "Default")
      (node (ref "RUSB2") (pin "2") (pinfunction "2_2") (pintype "passive"))
      (node (ref "X4") (pin "3") (pinfunction "3_3") (pintype "passive"))
    )
    (net (code "119") (name "Net-(U$1-CS)") (class "Default")
      (node (ref "R3") (pin "1") (pinfunction "1_1") (pintype "passive"))
      (node (ref "U$1") (pin "CE") (pinfunction "CS_CE") (pintype "bidirectional"))
    )
    (net (code "120") (name "Net-(U1-RATE)") (class "Default")
      (node (ref "RK5") (pin "1") (pinfunction "1_1") (pintype "passive"))
      (node (ref "SJ3") (pin "1") (pinfunction "1_1") (pintype "passive"))
      (node (ref "U1") (pin "15") (pinfunction "RATE_15") (pintype "bidirectional"))
    )
    (net (code "121") (name "Net-(U1-VBG)") (class "Default")
      (node (ref "C8") (pin "2") (pinfunction "2_2") (pintype "passive"))
      (node (ref "U1") (pin "6") (pinfunction "VBG_6") (pintype "bidirectional"))
    )
    (net (code "122") (name "Net-(U1-VFB)") (class "Default")
      (node (ref "20K") (pin "1") (pinfunction "1_1") (pintype "passive"))
      (node (ref "8.2K") (pin "2") (pinfunction "2_2") (pintype "passive"))
      (node (ref "U1") (pin "4") (pinfunction "VFB_4") (pintype "bidirectional"))
    )
    (net (code "123") (name "VDD") (class "Default")
      (node (ref "C1") (pin "1") (pinfunction "1_1") (pintype "passive"))
      (node (ref "CU3") (pin "1") (pinfunction "1_1") (pintype "passive"))
      (node (ref "CU7") (pin "1") (pinfunction "1_1") (pintype "passive"))
      (node (ref "D1") (pin "C") (pinfunction "C_C") (pintype "passive"))
      (node (ref "D2") (pin "C") (pinfunction "C_C") (pintype "passive"))
      (node (ref "D4") (pin "C") (pinfunction "C_C") (pintype "passive"))
      (node (ref "IC1") (pin "1") (pinfunction "VI_1") (pintype "input"))
      (node (ref "X3") (pin "1") (pinfunction "1_1") (pintype "passive"))
      (node (ref "X3") (pin "2") (pinfunction "1_2") (pintype "passive"))
    )
    (net (code "124") (name "VUSB") (class "Default")
      (node (ref "32U4") (pin "7") (pinfunction "VBUS_7") (pintype "bidirectional"))
      (node (ref "CU9") (pin "2") (pinfunction "2_2") (pintype "passive"))
      (node (ref "D4") (pin "A") (pinfunction "A_A") (pintype "passive"))
      (node (ref "X4") (pin "1") (pinfunction "1_1") (pintype "passive"))
    )
    (net (code "125") (name "unconnected-(IC4-HOME-Pad2)") (class "Default")
      (node (ref "IC4") (pin "2") (pinfunction "HOME_2") (pintype "bidirectional"))
    )
    (net (code "126") (name "unconnected-(IC6-HOME-Pad2)") (class "Default")
      (node (ref "IC6") (pin "2") (pinfunction "HOME_2") (pintype "bidirectional"))
    )
    (net (code "127") (name "unconnected-(J1-5-Pad+5V)") (class "Default")
      (node (ref "J1") (pin "+5V") (pinfunction "5_+5V") (pintype "bidirectional"))
    )
    (net (code "128") (name "unconnected-(J2-5-Pad+5V)") (class "Default")
      (node (ref "J2") (pin "+5V") (pinfunction "5_+5V") (pintype "bidirectional"))
    )
    (net (code "129") (name "unconnected-(U1-XO-Pad13)") (class "Default")
      (node (ref "U1") (pin "13") (pinfunction "XO_13") (pintype "bidirectional"))
    )
    (net (code "130") (name "unconnected-(U100-PadP$25)") (class "Default")
      (node (ref "U100") (pin "P$25") (pinfunction "P$25_P$25") (pintype "bidirectional"))
    )
    (net (code "131") (name "unconnected-(X4-Pad4)") (class "Default")
      (node (ref "X4") (pin "4") (pinfunction "4_4") (pintype "passive"))
    )
  )
)
